# STM32-E407_Rev_B1.net
KiCad netlist of a schematic drawn in EAGLE
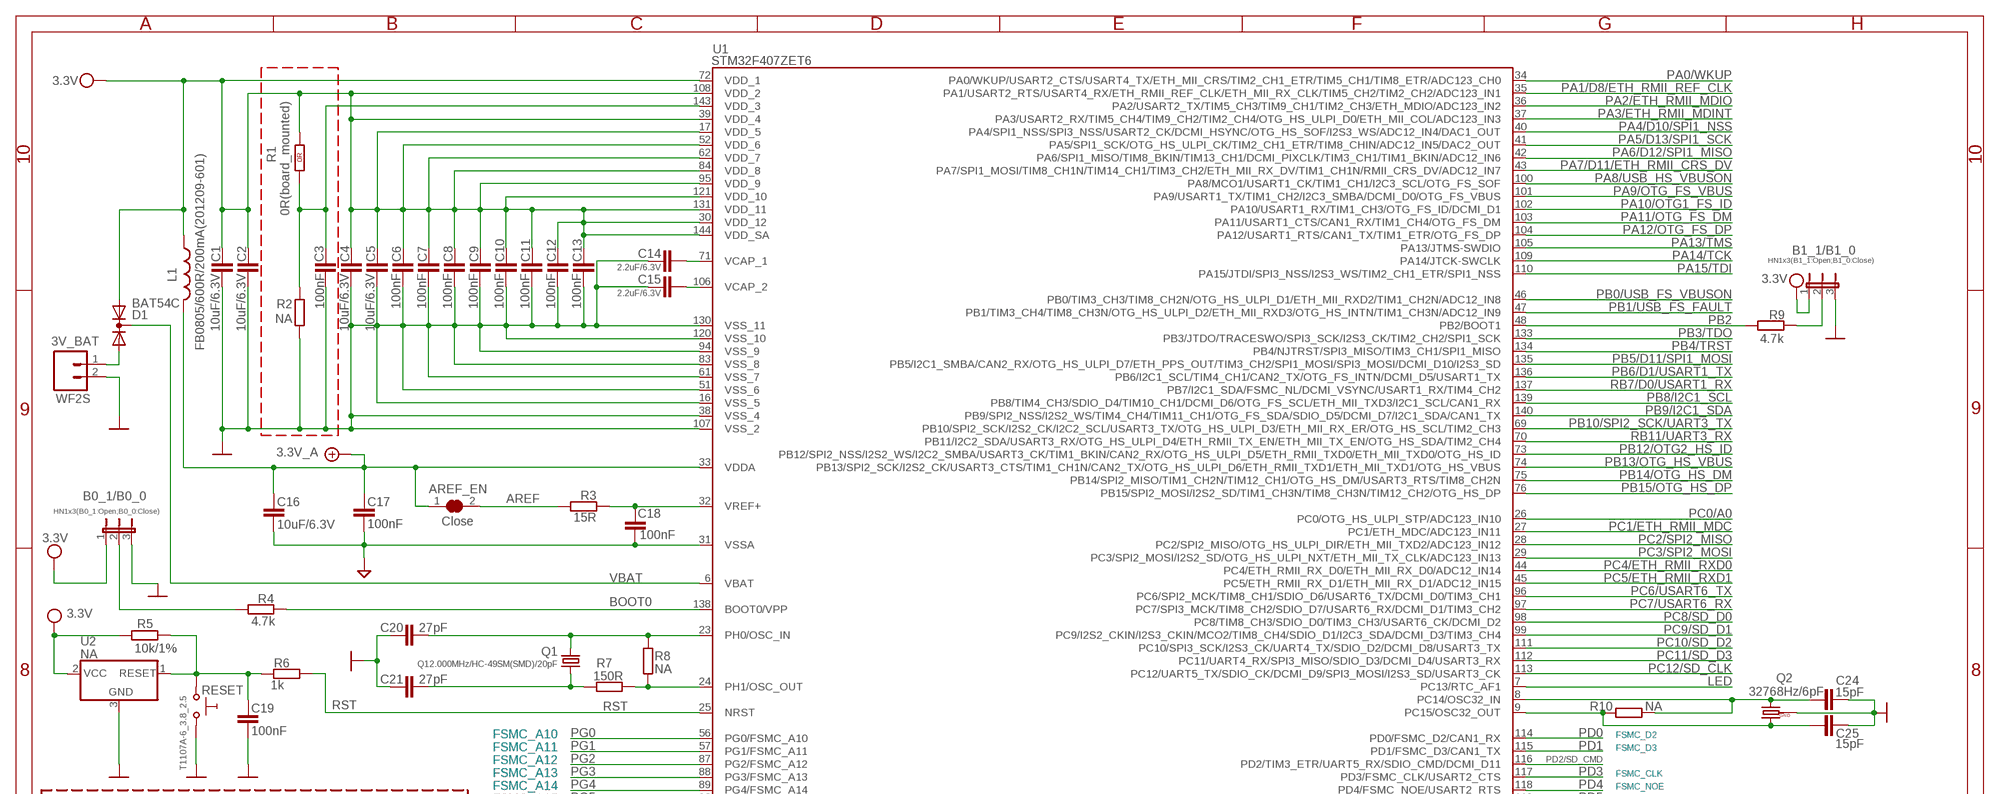
[diagram p0: schematic, sheet 1, part 1 of 2]
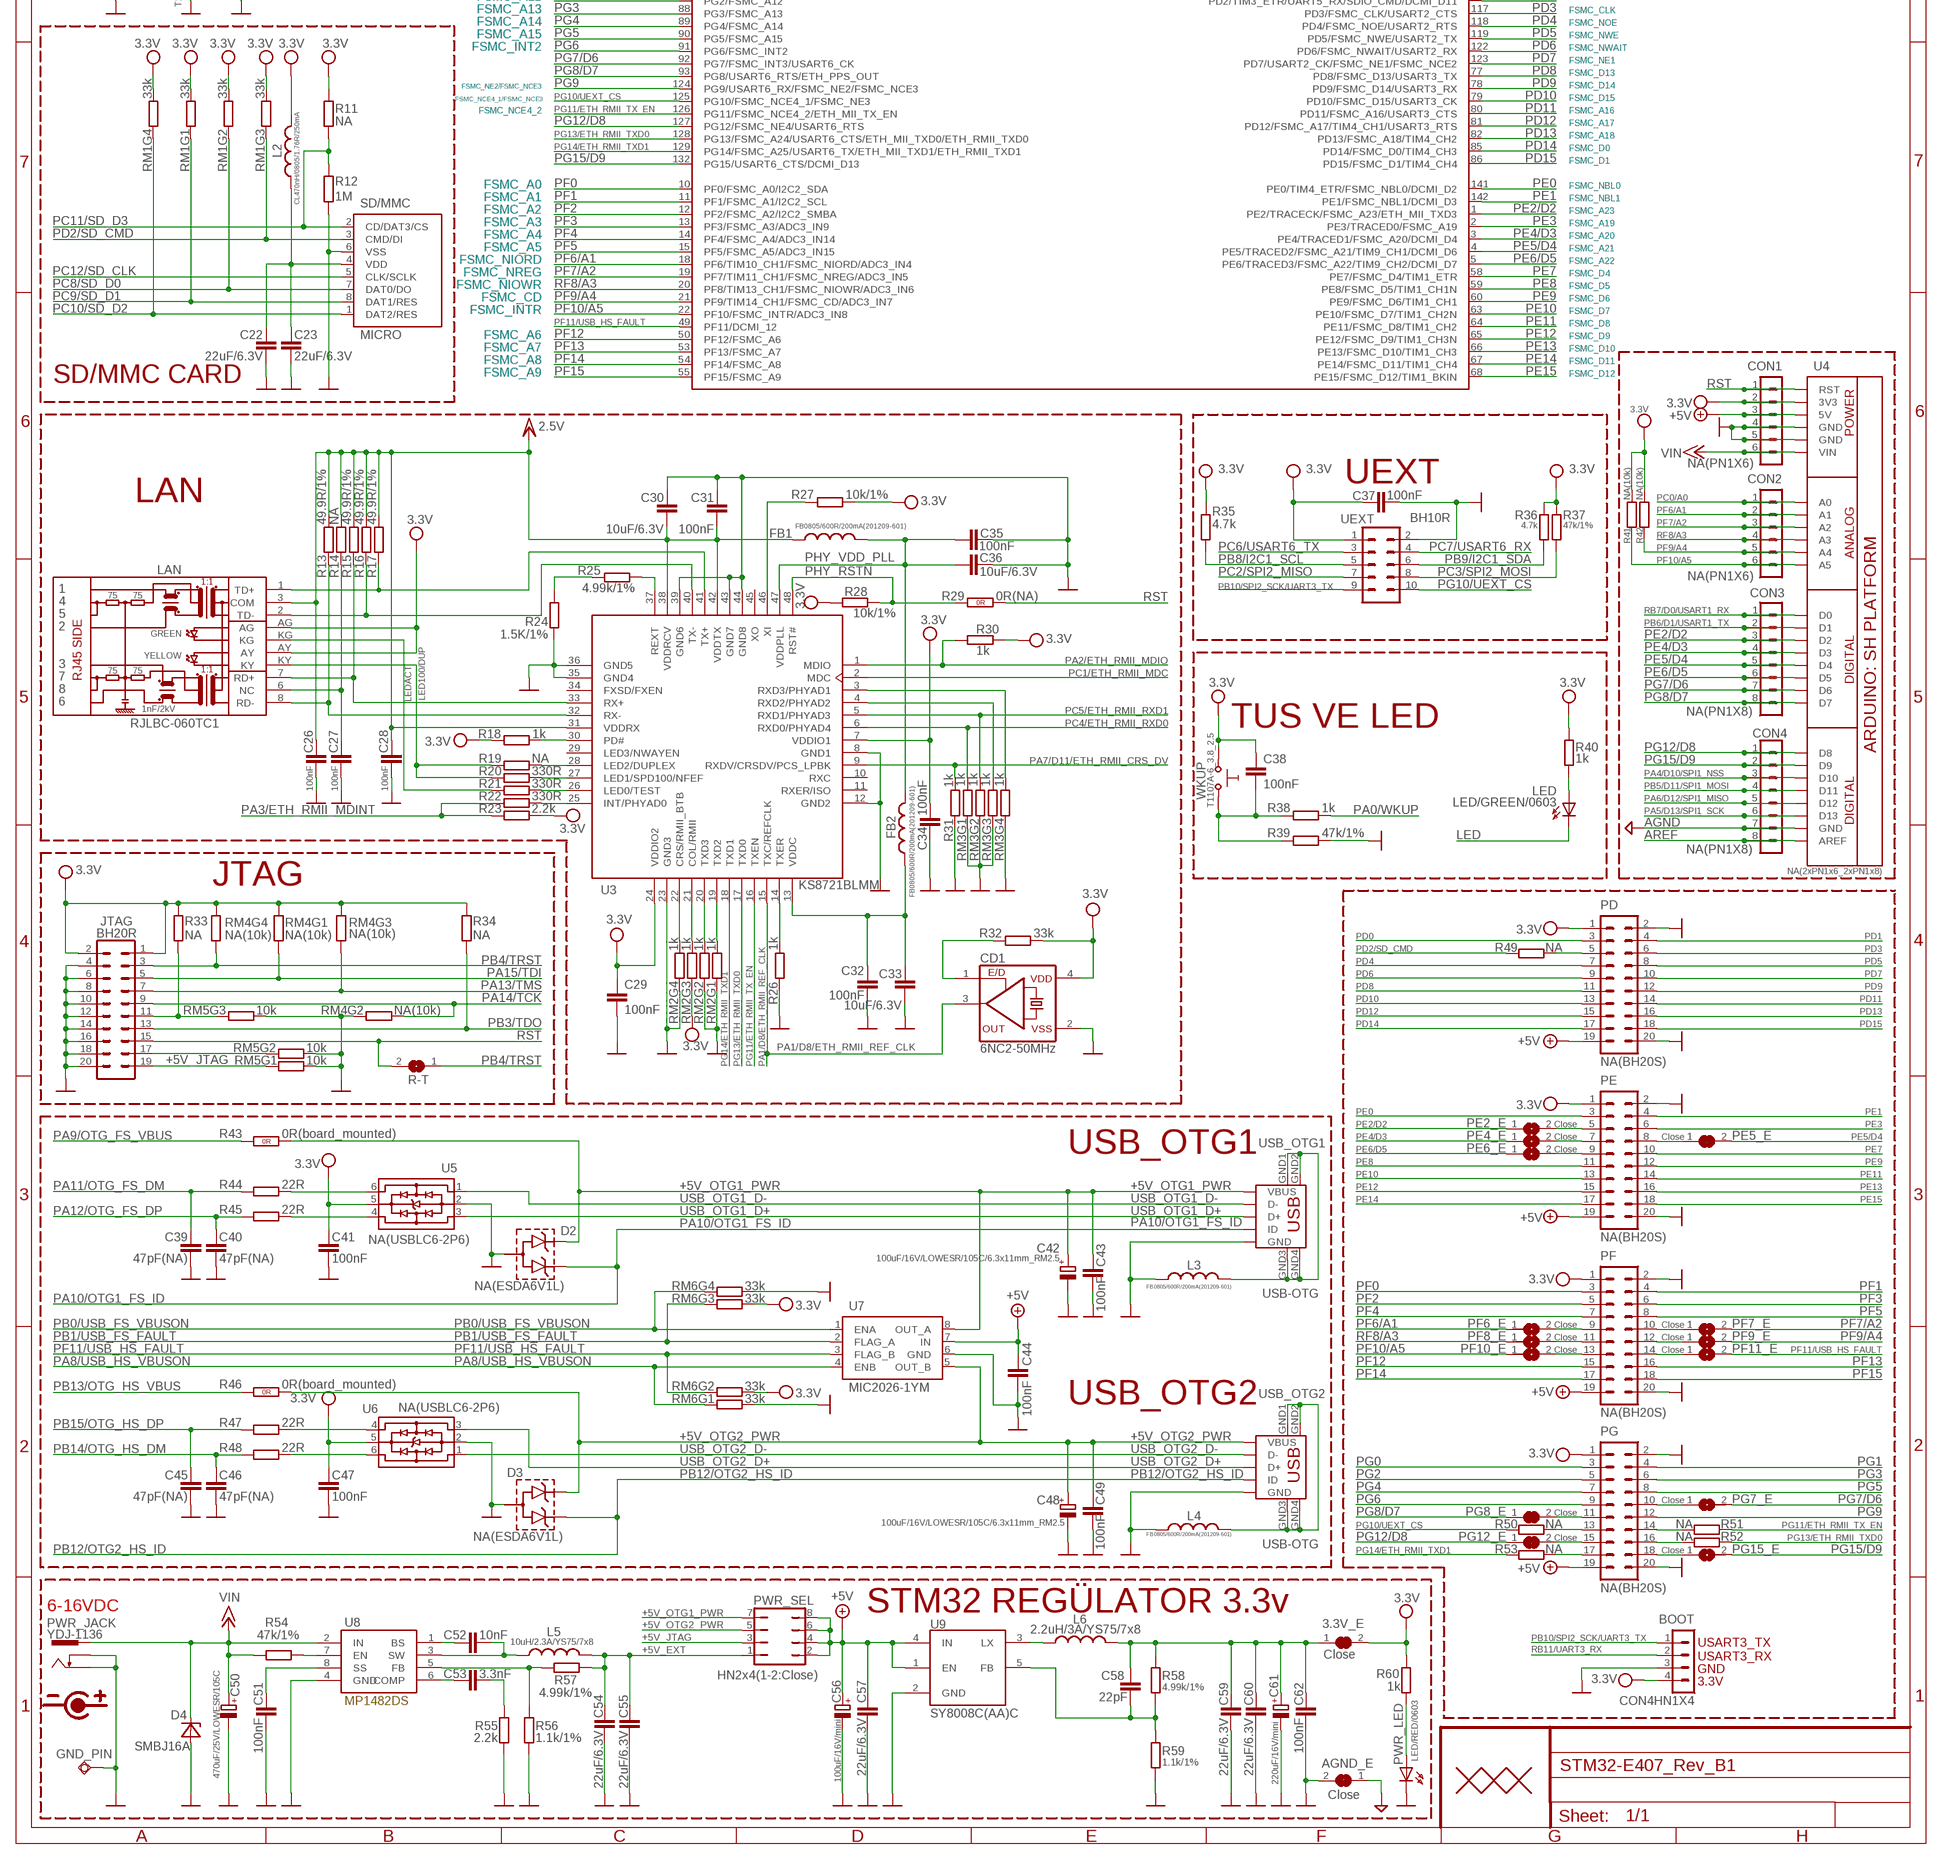
[diagram p1: schematic, sheet 1, part 2 of 2]

(export (version "E")
  (design (tool "Eeschema 10.0.6"))
  (components
    (comp (ref "3.3V_E")
      (value "Close")
      (footprint "eagle-import:SJ_1_SMALLER_CLOSE")
      (libsource (lib "eagle-import") (part "SJSJ_1_SMALLER_CLOSE"))
    )
    (comp (ref "3V_BAT")
      (value "WF2S")
      (footprint "eagle-import:CON2.54MM-2-0")
      (libsource (lib "eagle-import") (part "CON2PV2-2.54MM"))
    )
    (comp (ref "AGND_E")
      (value "Close")
      (footprint "eagle-import:SJ_1_SMALLER_CLOSE")
      (libsource (lib "eagle-import") (part "SJSJ_1_SMALLER_CLOSE"))
    )
    (comp (ref "AREF_EN")
      (value "Close")
      (footprint "eagle-import:SJ_1_SMALLER_CLOSE")
      (libsource (lib "eagle-import") (part "SJSJ_1_SMALLER_CLOSE"))
    )
    (comp (ref "B0_1/B0_0")
      (value "HN1x3(B0_1:Open;B0_0:Close)")
      (footprint "eagle-import:JP2")
      (libsource (lib "eagle-import") (part "JP2E"))
    )
    (comp (ref "B1_1/B1_0")
      (value "HN1x3(B1_1:Open;B1_0:Close)")
      (footprint "eagle-import:JP2")
      (libsource (lib "eagle-import") (part "JP2E"))
    )
    (comp (ref "BOOT")
      (value "CON4HN1X4")
      (footprint "eagle-import:HN1X4")
      (libsource (lib "eagle-import") (part "CON4HN1X4"))
    )
    (comp (ref "C1")
      (value "10uF/6.3V")
      (footprint "eagle-import:C0603_DWS")
      (libsource (lib "eagle-import") (part "C-EUC0603_DWS"))
    )
    (comp (ref "C2")
      (value "10uF/6.3V")
      (footprint "eagle-import:C0603_DWS")
      (libsource (lib "eagle-import") (part "C-EUC0603_DWS"))
    )
    (comp (ref "C3")
      (value "100nF")
      (footprint "eagle-import:C0603_DWS")
      (libsource (lib "eagle-import") (part "C-EUC0603_DWS"))
    )
    (comp (ref "C4")
      (value "10uF/6.3V")
      (footprint "eagle-import:C0603_DWS")
      (libsource (lib "eagle-import") (part "C-EUC0603_DWS"))
    )
    (comp (ref "C5")
      (value "10uF/6.3V")
      (footprint "eagle-import:C0603_DWS")
      (libsource (lib "eagle-import") (part "C-EUC0603_DWS"))
    )
    (comp (ref "C6")
      (value "100nF")
      (footprint "eagle-import:C0603_DWS")
      (libsource (lib "eagle-import") (part "C-EUC0603_DWS"))
    )
    (comp (ref "C7")
      (value "100nF")
      (footprint "eagle-import:C0603_DWS")
      (libsource (lib "eagle-import") (part "C-EUC0603_DWS"))
    )
    (comp (ref "C8")
      (value "100nF")
      (footprint "eagle-import:C0603_DWS")
      (libsource (lib "eagle-import") (part "C-EUC0603_DWS"))
    )
    (comp (ref "C9")
      (value "100nF")
      (footprint "eagle-import:C0603_DWS")
      (libsource (lib "eagle-import") (part "C-EUC0603_DWS"))
    )
    (comp (ref "C10")
      (value "100nF")
      (footprint "eagle-import:C0603_DWS")
      (libsource (lib "eagle-import") (part "C-EUC0603_DWS"))
    )
    (comp (ref "C11")
      (value "100nF")
      (footprint "eagle-import:C0603_DWS")
      (libsource (lib "eagle-import") (part "C-EUC0603_DWS"))
    )
    (comp (ref "C12")
      (value "100nF")
      (footprint "eagle-import:C0603_DWS")
      (libsource (lib "eagle-import") (part "C-EUC0603_DWS"))
    )
    (comp (ref "C13")
      (value "100nF")
      (footprint "eagle-import:C0603_DWS")
      (libsource (lib "eagle-import") (part "C-EUC0603_DWS"))
    )
    (comp (ref "C14")
      (value "2.2uF/6.3V")
      (footprint "eagle-import:C0603_DWS")
      (libsource (lib "eagle-import") (part "C-EUC0603_DWS"))
    )
    (comp (ref "C15")
      (value "2.2uF/6.3V")
      (footprint "eagle-import:C0603_DWS")
      (libsource (lib "eagle-import") (part "C-EUC0603_DWS"))
    )
    (comp (ref "C16")
      (value "10uF/6.3V")
      (footprint "eagle-import:C0603_DWS")
      (libsource (lib "eagle-import") (part "C-EUC0603_DWS"))
    )
    (comp (ref "C17")
      (value "100nF")
      (footprint "eagle-import:C0603_DWS")
      (libsource (lib "eagle-import") (part "C-EUC0603_DWS"))
    )
    (comp (ref "C18")
      (value "100nF")
      (footprint "eagle-import:C0603_DWS")
      (libsource (lib "eagle-import") (part "C-EUC0603_DWS"))
    )
    (comp (ref "C19")
      (value "100nF")
      (footprint "eagle-import:C0603_DWS")
      (libsource (lib "eagle-import") (part "C-EUC0603_DWS"))
    )
    (comp (ref "C20")
      (value "27pF")
      (footprint "eagle-import:C0603_DWS")
      (libsource (lib "eagle-import") (part "C-EUC0603_DWS"))
    )
    (comp (ref "C21")
      (value "27pF")
      (footprint "eagle-import:C0603_DWS")
      (libsource (lib "eagle-import") (part "C-EUC0603_DWS"))
    )
    (comp (ref "C22")
      (value "22uF/6.3V")
      (footprint "eagle-import:C0603_DWS")
      (libsource (lib "eagle-import") (part "C-EUC0603_DWS"))
    )
    (comp (ref "C23")
      (value "22uF/6.3V")
      (footprint "eagle-import:C0603_DWS")
      (libsource (lib "eagle-import") (part "C-EUC0603_DWS"))
    )
    (comp (ref "C24")
      (value "15pF")
      (footprint "eagle-import:C0603_DWS")
      (libsource (lib "eagle-import") (part "C-EUC0603_DWS"))
    )
    (comp (ref "C25")
      (value "15pF")
      (footprint "eagle-import:C0603_DWS")
      (libsource (lib "eagle-import") (part "C-EUC0603_DWS"))
    )
    (comp (ref "C26")
      (value "100nF")
      (footprint "eagle-import:C0603_DWS")
      (libsource (lib "eagle-import") (part "C-EUC0603_DWS"))
    )
    (comp (ref "C27")
      (value "100nF")
      (footprint "eagle-import:C0603_DWS")
      (libsource (lib "eagle-import") (part "C-EUC0603_DWS"))
    )
    (comp (ref "C28")
      (value "100nF")
      (footprint "eagle-import:C0603_DWS")
      (libsource (lib "eagle-import") (part "C-EUC0603_DWS"))
    )
    (comp (ref "C29")
      (value "100nF")
      (footprint "eagle-import:C0603_DWS")
      (libsource (lib "eagle-import") (part "C-EUC0603_DWS"))
    )
    (comp (ref "C30")
      (value "10uF/6.3V")
      (footprint "eagle-import:C0603_DWS")
      (libsource (lib "eagle-import") (part "C-EUC0603_DWS"))
    )
    (comp (ref "C31")
      (value "100nF")
      (footprint "eagle-import:C0603_DWS")
      (libsource (lib "eagle-import") (part "C-EUC0603_DWS"))
    )
    (comp (ref "C32")
      (value "100nF")
      (footprint "eagle-import:C0603_DWS")
      (libsource (lib "eagle-import") (part "C-EUC0603_DWS"))
    )
    (comp (ref "C33")
      (value "10uF/6.3V")
      (footprint "eagle-import:C0603_DWS")
      (libsource (lib "eagle-import") (part "C-EUC0603_DWS"))
    )
    (comp (ref "C34")
      (value "100nF")
      (footprint "eagle-import:C0603_DWS")
      (libsource (lib "eagle-import") (part "C-EUC0603_DWS"))
    )
    (comp (ref "C35")
      (value "100nF")
      (footprint "eagle-import:C0603_DWS")
      (libsource (lib "eagle-import") (part "C-EUC0603_DWS"))
    )
    (comp (ref "C36")
      (value "10uF/6.3V")
      (footprint "eagle-import:C0603_DWS")
      (libsource (lib "eagle-import") (part "C-EUC0603_DWS"))
    )
    (comp (ref "C37")
      (value "100nF")
      (footprint "eagle-import:C0603_DWS")
      (libsource (lib "eagle-import") (part "C-EUC0603_DWS"))
    )
    (comp (ref "C38")
      (value "100nF")
      (footprint "eagle-import:C0603_DWS")
      (libsource (lib "eagle-import") (part "C-EUC0603_DWS"))
    )
    (comp (ref "C39")
      (value "47pF(NA)")
      (footprint "eagle-import:C0603_DWS")
      (libsource (lib "eagle-import") (part "C-EUC0603_DWS"))
    )
    (comp (ref "C40")
      (value "47pF(NA)")
      (footprint "eagle-import:C0603_DWS")
      (libsource (lib "eagle-import") (part "C-EUC0603_DWS"))
    )
    (comp (ref "C41")
      (value "100nF")
      (footprint "eagle-import:C0603_DWS")
      (libsource (lib "eagle-import") (part "C-EUC0603_DWS"))
    )
    (comp (ref "C42")
      (value "100uF/16V/LOWESR/105C/6.3x11mm_RM2.5")
      (footprint "eagle-import:E2,5-6,3")
      (libsource (lib "eagle-import") (part "CPOL-EUE2.5-6.3"))
    )
    (comp (ref "C43")
      (value "100nF")
      (footprint "eagle-import:C0603_DWS")
      (libsource (lib "eagle-import") (part "C-EUC0603_DWS"))
    )
    (comp (ref "C44")
      (value "100nF")
      (footprint "eagle-import:C0603_DWS")
      (libsource (lib "eagle-import") (part "C-EUC0603_DWS"))
    )
    (comp (ref "C45")
      (value "47pF(NA)")
      (footprint "eagle-import:C0603_DWS")
      (libsource (lib "eagle-import") (part "C-EUC0603_DWS"))
    )
    (comp (ref "C46")
      (value "47pF(NA)")
      (footprint "eagle-import:C0603_DWS")
      (libsource (lib "eagle-import") (part "C-EUC0603_DWS"))
    )
    (comp (ref "C47")
      (value "100nF")
      (footprint "eagle-import:C0603_DWS")
      (libsource (lib "eagle-import") (part "C-EUC0603_DWS"))
    )
    (comp (ref "C48")
      (value "100uF/16V/LOWESR/105C/6.3x11mm_RM2.5")
      (footprint "eagle-import:E2,5-6,3")
      (libsource (lib "eagle-import") (part "CPOL-EUE2.5-6.3"))
    )
    (comp (ref "C49")
      (value "100nF")
      (footprint "eagle-import:C0603_DWS")
      (libsource (lib "eagle-import") (part "C-EUC0603_DWS"))
    )
    (comp (ref "C50")
      (value "470uF/25V/LOWESR/105C")
      (footprint "eagle-import:E5-10,5")
      (libsource (lib "eagle-import") (part "CPOL-EUE5-10.5"))
    )
    (comp (ref "C51")
      (value "100nF")
      (footprint "eagle-import:C0603_DWS")
      (libsource (lib "eagle-import") (part "C-EUC0603_DWS"))
    )
    (comp (ref "C52")
      (value "10nF")
      (footprint "eagle-import:C0603_DWS")
      (libsource (lib "eagle-import") (part "C-EUC0603_DWS"))
    )
    (comp (ref "C53")
      (value "3.3nF")
      (footprint "eagle-import:C0603_DWS")
      (libsource (lib "eagle-import") (part "C-EUC0603_DWS"))
    )
    (comp (ref "C54")
      (value "22uF/6.3V")
      (footprint "eagle-import:C0603_DWS")
      (libsource (lib "eagle-import") (part "C-EUC0603_DWS"))
    )
    (comp (ref "C55")
      (value "22uF/6.3V")
      (footprint "eagle-import:C0603_DWS")
      (libsource (lib "eagle-import") (part "C-EUC0603_DWS"))
    )
    (comp (ref "C56")
      (value "100uF/16V/mini")
      (footprint "eagle-import:E2,5-6")
      (libsource (lib "eagle-import") (part "CPOL-EUE2.5-6"))
    )
    (comp (ref "C57")
      (value "22uF/6.3V")
      (footprint "eagle-import:C0603_DWS")
      (libsource (lib "eagle-import") (part "C-EUC0603_DWS"))
    )
    (comp (ref "C58")
      (value "22pF")
      (footprint "eagle-import:C0603_DWS")
      (libsource (lib "eagle-import") (part "C-EUC0603_DWS"))
    )
    (comp (ref "C59")
      (value "22uF/6.3V")
      (footprint "eagle-import:C0603_DWS")
      (libsource (lib "eagle-import") (part "C-EUC0603_DWS"))
    )
    (comp (ref "C60")
      (value "22uF/6.3V")
      (footprint "eagle-import:C0603_DWS")
      (libsource (lib "eagle-import") (part "C-EUC0603_DWS"))
    )
    (comp (ref "C61")
      (value "220uF/16V/mini")
      (footprint "eagle-import:E3,5-8")
      (libsource (lib "eagle-import") (part "CPOL-EUE3.5-8"))
    )
    (comp (ref "C62")
      (value "100nF")
      (footprint "eagle-import:C0603_DWS")
      (libsource (lib "eagle-import") (part "C-EUC0603_DWS"))
    )
    (comp (ref "CD1")
      (value "6NC2-50MHz")
      (footprint "eagle-import:7X5MM_CLOCK_DRIVER")
      (libsource (lib "eagle-import") (part "6NC2_CLOCK_DRIVER"))
    )
    (comp (ref "CON1")
      (value "NA(PN1X6)")
      (footprint "eagle-import:PN1X6")
      (libsource (lib "eagle-import") (part "CON6PN1X6"))
    )
    (comp (ref "CON2")
      (value "NA(PN1X6)")
      (footprint "eagle-import:PN1X6")
      (libsource (lib "eagle-import") (part "CON6PN1X6"))
    )
    (comp (ref "CON3")
      (value "NA(PN1X8)")
      (footprint "eagle-import:PN1X8")
      (libsource (lib "eagle-import") (part "CON8PN1X8"))
    )
    (comp (ref "CON4")
      (value "NA(PN1X8)")
      (footprint "eagle-import:PN1X8")
      (libsource (lib "eagle-import") (part "CON8PN1X8"))
    )
    (comp (ref "D1")
      (value "BAT54C")
      (footprint "eagle-import:SOT23C")
      (libsource (lib "eagle-import") (part "DIODE_AC-CA_"))
    )
    (comp (ref "D2")
      (value "NA(ESDA6V1L)")
      (footprint "eagle-import:SOT-23")
      (libsource (lib "eagle-import") (part "MMBZ5V6ALT1"))
    )
    (comp (ref "D3")
      (value "NA(ESDA6V1L)")
      (footprint "eagle-import:SOT-23")
      (libsource (lib "eagle-import") (part "MMBZ5V6ALT1"))
    )
    (comp (ref "D4")
      (value "SMBJ16A")
      (footprint "eagle-import:DO214AA")
      (libsource (lib "eagle-import") (part "SMBJ16A"))
    )
    (comp (ref "FB1")
      (value "FB0805/600R/200mA(201209-601)")
      (footprint "eagle-import:L0805_5MIL_DWS")
      (libsource (lib "eagle-import") (part "L-USL0805_5MIL_DWS"))
    )
    (comp (ref "FB2")
      (value "FB0805/600R/200mA(201209-601)")
      (footprint "eagle-import:L0805_5MIL_DWS")
      (libsource (lib "eagle-import") (part "L-USL0805_5MIL_DWS"))
    )
    (comp (ref "GND_PIN")
      (value "TESTPAD3")
      (footprint "eagle-import:TEST_PAD40_70_SQUARE")
      (libsource (lib "eagle-import") (part "TESTPAD3"))
    )
    (comp (ref "JTAG")
      (value "BH20R")
      (footprint "eagle-import:BH20R")
      (libsource (lib "eagle-import") (part "ML20R"))
    )
    (comp (ref "L1")
      (value "FB0805/600R/200mA(201209-601)")
      (footprint "eagle-import:L0805_5MIL_DWS")
      (libsource (lib "eagle-import") (part "L-USL0805_5MIL_DWS"))
    )
    (comp (ref "L2")
      (value "CL470nH/0805/1.76R/250mA")
      (footprint "eagle-import:L0805_5MIL_DWS")
      (libsource (lib "eagle-import") (part "L-USL0805_5MIL_DWS"))
    )
    (comp (ref "L3")
      (value "FB0805/600R/200mA(201209-601)")
      (footprint "eagle-import:L0805_5MIL_DWS")
      (libsource (lib "eagle-import") (part "L-USL0805_5MIL_DWS"))
    )
    (comp (ref "L4")
      (value "FB0805/600R/200mA(201209-601)")
      (footprint "eagle-import:L0805_5MIL_DWS")
      (libsource (lib "eagle-import") (part "L-USL0805_5MIL_DWS"))
    )
    (comp (ref "L5")
      (value "10uH/2.3A/YS75/7x8")
      (footprint "eagle-import:L7078")
      (libsource (lib "eagle-import") (part "L-USL7078"))
    )
    (comp (ref "L6")
      (value "2.2uH/3A/YS75/7x8")
      (footprint "eagle-import:L7078")
      (libsource (lib "eagle-import") (part "L-USL7078"))
    )
    (comp (ref "LAN")
      (value "RJLBC-060TC1")
      (footprint "eagle-import:RJLBC-060TC1")
      (libsource (lib "eagle-import") (part "RJLBC-060TC1"))
    )
    (comp (ref "LED")
      (value "LED/GREEN/0603")
      (footprint "eagle-import:LED-0603")
      (libsource (lib "eagle-import") (part "LED0603DWS"))
    )
    (comp (ref "PD")
      (value "NA(BH20S)")
      (footprint "eagle-import:ML20-MALE")
      (libsource (lib "eagle-import") (part "ML20"))
    )
    (comp (ref "PE")
      (value "NA(BH20S)")
      (footprint "eagle-import:ML20-MALE")
      (libsource (lib "eagle-import") (part "ML20"))
    )
    (comp (ref "PE2_E")
      (value "Close")
      (footprint "eagle-import:SJ_1_SMALLER_CLOSE")
      (libsource (lib "eagle-import") (part "SJSJ_1_SMALLER_CLOSE"))
    )
    (comp (ref "PE4_E")
      (value "Close")
      (footprint "eagle-import:SJ_1_SMALLER_CLOSE")
      (libsource (lib "eagle-import") (part "SJSJ_1_SMALLER_CLOSE"))
    )
    (comp (ref "PE5_E")
      (value "Close")
      (footprint "eagle-import:SJ_1_SMALLER_CLOSE")
      (libsource (lib "eagle-import") (part "SJSJ_1_SMALLER_CLOSE"))
    )
    (comp (ref "PE6_E")
      (value "Close")
      (footprint "eagle-import:SJ_1_SMALLER_CLOSE")
      (libsource (lib "eagle-import") (part "SJSJ_1_SMALLER_CLOSE"))
    )
    (comp (ref "PF")
      (value "NA(BH20S)")
      (footprint "eagle-import:ML20-MALE")
      (libsource (lib "eagle-import") (part "ML20"))
    )
    (comp (ref "PF6_E")
      (value "Close")
      (footprint "eagle-import:SJ_1_SMALLER_CLOSE")
      (libsource (lib "eagle-import") (part "SJSJ_1_SMALLER_CLOSE"))
    )
    (comp (ref "PF7_E")
      (value "Close")
      (footprint "eagle-import:SJ_1_SMALLER_CLOSE")
      (libsource (lib "eagle-import") (part "SJSJ_1_SMALLER_CLOSE"))
    )
    (comp (ref "PF8_E")
      (value "Close")
      (footprint "eagle-import:SJ_1_SMALLER_CLOSE")
      (libsource (lib "eagle-import") (part "SJSJ_1_SMALLER_CLOSE"))
    )
    (comp (ref "PF9_E")
      (value "Close")
      (footprint "eagle-import:SJ_1_SMALLER_CLOSE")
      (libsource (lib "eagle-import") (part "SJSJ_1_SMALLER_CLOSE"))
    )
    (comp (ref "PF10_E")
      (value "Close")
      (footprint "eagle-import:SJ_1_SMALLER_CLOSE")
      (libsource (lib "eagle-import") (part "SJSJ_1_SMALLER_CLOSE"))
    )
    (comp (ref "PF11_E")
      (value "Close")
      (footprint "eagle-import:SJ_1_SMALLER_CLOSE")
      (libsource (lib "eagle-import") (part "SJSJ_1_SMALLER_CLOSE"))
    )
    (comp (ref "PG")
      (value "NA(BH20S)")
      (footprint "eagle-import:ML20-MALE")
      (libsource (lib "eagle-import") (part "ML20"))
    )
    (comp (ref "PG7_E")
      (value "Close")
      (footprint "eagle-import:SJ_1_SMALLER_CLOSE")
      (libsource (lib "eagle-import") (part "SJSJ_1_SMALLER_CLOSE"))
    )
    (comp (ref "PG8_E")
      (value "Close")
      (footprint "eagle-import:SJ_1_SMALLER_CLOSE")
      (libsource (lib "eagle-import") (part "SJSJ_1_SMALLER_CLOSE"))
    )
    (comp (ref "PG12_E")
      (value "Close")
      (footprint "eagle-import:SJ_1_SMALLER_CLOSE")
      (libsource (lib "eagle-import") (part "SJSJ_1_SMALLER_CLOSE"))
    )
    (comp (ref "PG15_E")
      (value "Close")
      (footprint "eagle-import:SJ_1_SMALLER_CLOSE")
      (libsource (lib "eagle-import") (part "SJSJ_1_SMALLER_CLOSE"))
    )
    (comp (ref "PWR_JACK")
      (value "YDJ-1136")
      (footprint "eagle-import:PWR_JACK_UNI_MILLING")
      (libsource (lib "eagle-import") (part "PWR-JAKPWR_JACK_UNI_MILLING"))
    )
    (comp (ref "PWR_LED")
      (value "LED/RED/0603")
      (footprint "eagle-import:LED-0603")
      (libsource (lib "eagle-import") (part "LED0603DWS"))
    )
    (comp (ref "PWR_SEL")
      (value "HN2x4(1-2:Close)")
      (footprint "eagle-import:JP4Q_2")
      (libsource (lib "eagle-import") (part "JP4QNEW"))
    )
    (comp (ref "Q1")
      (value "Q12.000MHz/HC-49SM(SMD)/20pF")
      (footprint "eagle-import:HC49_SMD2_THIN")
      (libsource (lib "eagle-import") (part "HC49/S1"))
    )
    (comp (ref "Q2")
      (value "32768Hz/6pF")
      (footprint "eagle-import:TC26H_3_REPAIR_SMD")
      (libsource (lib "eagle-import") (part "Q_GND1"))
    )
    (comp (ref "R-T")
      (value "Open")
      (footprint "eagle-import:SJ_1_SMALLER")
      (libsource (lib "eagle-import") (part "SJSJ_SMALLER"))
    )
    (comp (ref "R1")
      (value "0R(board_mounted)")
      (footprint "eagle-import:0603_0R")
      (libsource (lib "eagle-import") (part "R_0R0R(NA)"))
    )
    (comp (ref "R2")
      (value "NA")
      (footprint "eagle-import:R0603_5MIL_DWS_NA")
      (libsource (lib "eagle-import") (part "R-EU_R0603_5MIL_DWS_NA"))
    )
    (comp (ref "R3")
      (value "15R")
      (footprint "eagle-import:R0603_5MIL_DWS")
      (libsource (lib "eagle-import") (part "R-EU_R0603_5MIL_DWS"))
    )
    (comp (ref "R4")
      (value "4.7k")
      (footprint "eagle-import:R0603_5MIL_DWS")
      (libsource (lib "eagle-import") (part "R-EU_R0603_5MIL_DWS"))
    )
    (comp (ref "R5")
      (value "10k/1%")
      (footprint "eagle-import:R0603_5MIL_DWS")
      (libsource (lib "eagle-import") (part "R-EU_R0603_5MIL_DWS"))
    )
    (comp (ref "R6")
      (value "1k")
      (footprint "eagle-import:R0603_5MIL_DWS")
      (libsource (lib "eagle-import") (part "R-EU_R0603_5MIL_DWS"))
    )
    (comp (ref "R7")
      (value "150R")
      (footprint "eagle-import:R0603_5MIL_DWS")
      (libsource (lib "eagle-import") (part "R-EU_R0603_5MIL_DWS"))
    )
    (comp (ref "R8")
      (value "NA")
      (footprint "eagle-import:R0603_5MIL_DWS_NA")
      (libsource (lib "eagle-import") (part "R-EU_R0603_5MIL_DWS_NA"))
    )
    (comp (ref "R9")
      (value "4.7k")
      (footprint "eagle-import:R0603_5MIL_DWS")
      (libsource (lib "eagle-import") (part "R-EU_R0603_5MIL_DWS"))
    )
    (comp (ref "R10")
      (value "NA")
      (footprint "eagle-import:R0603_5MIL_DWS_NA")
      (libsource (lib "eagle-import") (part "R-EU_R0603_5MIL_DWS_NA"))
    )
    (comp (ref "R11")
      (value "NA")
      (footprint "eagle-import:R0603_5MIL_DWS_NA")
      (libsource (lib "eagle-import") (part "R-EU_R0603_5MIL_DWS_NA"))
    )
    (comp (ref "R12")
      (value "1M")
      (footprint "eagle-import:R0603_5MIL_DWS")
      (libsource (lib "eagle-import") (part "R-EU_R0603_5MIL_DWS"))
    )
    (comp (ref "R13")
      (value "49.9R/1%")
      (footprint "eagle-import:R0603_5MIL_DWS")
      (libsource (lib "eagle-import") (part "R-EU_R0603_5MIL_DWS"))
    )
    (comp (ref "R14")
      (value "NA")
      (footprint "eagle-import:R0603_5MIL_DWS_NA")
      (libsource (lib "eagle-import") (part "R-EU_R0603_5MIL_DWS_NA"))
    )
    (comp (ref "R15")
      (value "49.9R/1%")
      (footprint "eagle-import:R0603_5MIL_DWS")
      (libsource (lib "eagle-import") (part "R-EU_R0603_5MIL_DWS"))
    )
    (comp (ref "R16")
      (value "49.9R/1%")
      (footprint "eagle-import:R0603_5MIL_DWS")
      (libsource (lib "eagle-import") (part "R-EU_R0603_5MIL_DWS"))
    )
    (comp (ref "R17")
      (value "49.9R/1%")
      (footprint "eagle-import:R0603_5MIL_DWS")
      (libsource (lib "eagle-import") (part "R-EU_R0603_5MIL_DWS"))
    )
    (comp (ref "R18")
      (value "1k")
      (footprint "eagle-import:R0603_5MIL_DWS")
      (libsource (lib "eagle-import") (part "R-EU_R0603_5MIL_DWS"))
    )
    (comp (ref "R19")
      (value "NA")
      (footprint "eagle-import:R0603_5MIL_DWS_NA")
      (libsource (lib "eagle-import") (part "R-EU_R0603_5MIL_DWS_NA"))
    )
    (comp (ref "R20")
      (value "330R")
      (footprint "eagle-import:R0603_5MIL_DWS")
      (libsource (lib "eagle-import") (part "R-EU_R0603_5MIL_DWS"))
    )
    (comp (ref "R21")
      (value "330R")
      (footprint "eagle-import:R0603_5MIL_DWS")
      (libsource (lib "eagle-import") (part "R-EU_R0603_5MIL_DWS"))
    )
    (comp (ref "R22")
      (value "330R")
      (footprint "eagle-import:R0603_5MIL_DWS")
      (libsource (lib "eagle-import") (part "R-EU_R0603_5MIL_DWS"))
    )
    (comp (ref "R23")
      (value "2.2k")
      (footprint "eagle-import:R0603_5MIL_DWS")
      (libsource (lib "eagle-import") (part "R-EU_R0603_5MIL_DWS"))
    )
    (comp (ref "R24")
      (value "1.5K/1%")
      (footprint "eagle-import:R0603_5MIL_DWS")
      (libsource (lib "eagle-import") (part "R-EU_R0603_5MIL_DWS"))
    )
    (comp (ref "R25")
      (value "4.99k/1%")
      (footprint "eagle-import:R0603_5MIL_DWS")
      (libsource (lib "eagle-import") (part "R-EU_R0603_5MIL_DWS"))
    )
    (comp (ref "R26")
      (value "1k")
      (footprint "eagle-import:R0603_5MIL_DWS")
      (libsource (lib "eagle-import") (part "R-EU_R0603_5MIL_DWS"))
    )
    (comp (ref "R27")
      (value "10k/1%")
      (footprint "eagle-import:R0603_5MIL_DWS")
      (libsource (lib "eagle-import") (part "R-EU_R0603_5MIL_DWS"))
    )
    (comp (ref "R28")
      (value "10k/1%")
      (footprint "eagle-import:R0603_5MIL_DWS")
      (libsource (lib "eagle-import") (part "R-EU_R0603_5MIL_DWS"))
    )
    (comp (ref "R29")
      (value "0R(NA)")
      (footprint "eagle-import:0603_0R")
      (libsource (lib "eagle-import") (part "R_0R0R(NA)"))
    )
    (comp (ref "R30")
      (value "1k")
      (footprint "eagle-import:R0603_5MIL_DWS")
      (libsource (lib "eagle-import") (part "R-EU_R0603_5MIL_DWS"))
    )
    (comp (ref "R31")
      (value "1k")
      (footprint "eagle-import:R0603_5MIL_DWS")
      (libsource (lib "eagle-import") (part "R-EU_R0603_5MIL_DWS"))
    )
    (comp (ref "R32")
      (value "33k")
      (footprint "eagle-import:R0603_5MIL_DWS")
      (libsource (lib "eagle-import") (part "R-EU_R0603_5MIL_DWS"))
    )
    (comp (ref "R33")
      (value "NA")
      (footprint "eagle-import:R0603_5MIL_DWS_NA")
      (libsource (lib "eagle-import") (part "R-EU_R0603_5MIL_DWS_NA"))
    )
    (comp (ref "R34")
      (value "NA")
      (footprint "eagle-import:R0603_5MIL_DWS_NA")
      (libsource (lib "eagle-import") (part "R-EU_R0603_5MIL_DWS_NA"))
    )
    (comp (ref "R35")
      (value "4.7k")
      (footprint "eagle-import:R0603_5MIL_DWS")
      (libsource (lib "eagle-import") (part "R-EU_R0603_5MIL_DWS"))
    )
    (comp (ref "R36")
      (value "4.7k")
      (footprint "eagle-import:R0603_5MIL_DWS")
      (libsource (lib "eagle-import") (part "R-EU_R0603_5MIL_DWS"))
    )
    (comp (ref "R37")
      (value "47k/1%")
      (footprint "eagle-import:R0603_5MIL_DWS")
      (libsource (lib "eagle-import") (part "R-EU_R0603_5MIL_DWS"))
    )
    (comp (ref "R38")
      (value "1k")
      (footprint "eagle-import:R0603_5MIL_DWS")
      (libsource (lib "eagle-import") (part "R-EU_R0603_5MIL_DWS"))
    )
    (comp (ref "R39")
      (value "47k/1%")
      (footprint "eagle-import:R0603_5MIL_DWS")
      (libsource (lib "eagle-import") (part "R-EU_R0603_5MIL_DWS"))
    )
    (comp (ref "R40")
      (value "1k")
      (footprint "eagle-import:R0603_5MIL_DWS")
      (libsource (lib "eagle-import") (part "R-EU_R0603_5MIL_DWS"))
    )
    (comp (ref "R41")
      (value "NA(10k)")
      (footprint "eagle-import:R0603_5MIL_DWS_NA")
      (libsource (lib "eagle-import") (part "R-EU_R0603_5MIL_DWS_NA"))
    )
    (comp (ref "R42")
      (value "NA(10k)")
      (footprint "eagle-import:R0603_5MIL_DWS_NA")
      (libsource (lib "eagle-import") (part "R-EU_R0603_5MIL_DWS_NA"))
    )
    (comp (ref "R43")
      (value "0R(board_mounted)")
      (footprint "eagle-import:0603_0R")
      (libsource (lib "eagle-import") (part "R_0R0R(NA)"))
    )
    (comp (ref "R44")
      (value "22R")
      (footprint "eagle-import:R0603_5MIL_DWS")
      (libsource (lib "eagle-import") (part "R-EU_R0603_5MIL_DWS"))
    )
    (comp (ref "R45")
      (value "22R")
      (footprint "eagle-import:R0603_5MIL_DWS")
      (libsource (lib "eagle-import") (part "R-EU_R0603_5MIL_DWS"))
    )
    (comp (ref "R46")
      (value "0R(board_mounted)")
      (footprint "eagle-import:0603_0R")
      (libsource (lib "eagle-import") (part "R_0R0R(NA)"))
    )
    (comp (ref "R47")
      (value "22R")
      (footprint "eagle-import:R0603_5MIL_DWS")
      (libsource (lib "eagle-import") (part "R-EU_R0603_5MIL_DWS"))
    )
    (comp (ref "R48")
      (value "22R")
      (footprint "eagle-import:R0603_5MIL_DWS")
      (libsource (lib "eagle-import") (part "R-EU_R0603_5MIL_DWS"))
    )
    (comp (ref "R49")
      (value "NA")
      (footprint "eagle-import:R0603_5MIL_DWS")
      (libsource (lib "eagle-import") (part "R-EU_R0603_5MIL_DWS"))
    )
    (comp (ref "R50")
      (value "NA")
      (footprint "eagle-import:R0603_5MIL_DWS")
      (libsource (lib "eagle-import") (part "R-EU_R0603_5MIL_DWS"))
    )
    (comp (ref "R51")
      (value "NA")
      (footprint "eagle-import:R0603_5MIL_DWS")
      (libsource (lib "eagle-import") (part "R-EU_R0603_5MIL_DWS"))
    )
    (comp (ref "R52")
      (value "NA")
      (footprint "eagle-import:R0603_5MIL_DWS")
      (libsource (lib "eagle-import") (part "R-EU_R0603_5MIL_DWS"))
    )
    (comp (ref "R53")
      (value "NA")
      (footprint "eagle-import:R0603_5MIL_DWS")
      (libsource (lib "eagle-import") (part "R-EU_R0603_5MIL_DWS"))
    )
    (comp (ref "R54")
      (value "47k/1%")
      (footprint "eagle-import:R0603_5MIL_DWS")
      (libsource (lib "eagle-import") (part "R-EU_R0603_5MIL_DWS"))
    )
    (comp (ref "R55")
      (value "2.2k")
      (footprint "eagle-import:R0603_5MIL_DWS")
      (libsource (lib "eagle-import") (part "R-EU_R0603_5MIL_DWS"))
    )
    (comp (ref "R56")
      (value "1.1k/1%")
      (footprint "eagle-import:R0603_5MIL_DWS")
      (libsource (lib "eagle-import") (part "R-EU_R0603_5MIL_DWS"))
    )
    (comp (ref "R57")
      (value "4.99k/1%")
      (footprint "eagle-import:R0603_5MIL_DWS")
      (libsource (lib "eagle-import") (part "R-EU_R0603_5MIL_DWS"))
    )
    (comp (ref "R58")
      (value "4.99k/1%")
      (footprint "eagle-import:R0603_5MIL_DWS")
      (libsource (lib "eagle-import") (part "R-EU_R0603_5MIL_DWS"))
    )
    (comp (ref "R59")
      (value "1.1k/1%")
      (footprint "eagle-import:R0603_5MIL_DWS")
      (libsource (lib "eagle-import") (part "R-EU_R0603_5MIL_DWS"))
    )
    (comp (ref "R60")
      (value "1k")
      (footprint "eagle-import:R0603_5MIL_DWS")
      (libsource (lib "eagle-import") (part "R-EU_R0603_5MIL_DWS"))
    )
    (comp (ref "RESET")
      (value "T1107A-6_3.8_2.5")
      (footprint "eagle-import:SW-TAKT_6X3.5_SMD")
      (libsource (lib "eagle-import") (part "SW-TAKT6"))
    )
    (comp (ref "RM1")
      (value "33k")
      (footprint "eagle-import:R_MATRIX_4")
      (libsource (lib "eagle-import") (part "R_MATRIX_4E"))
    )
    (comp (ref "RM2")
      (value "1k")
      (footprint "eagle-import:R_MATRIX_4")
      (libsource (lib "eagle-import") (part "R_MATRIX_4E"))
    )
    (comp (ref "RM3")
      (value "1k")
      (footprint "eagle-import:R_MATRIX_4")
      (libsource (lib "eagle-import") (part "R_MATRIX_4E"))
    )
    (comp (ref "RM4")
      (value "NA(10k)")
      (footprint "eagle-import:R_MATRIX_4")
      (libsource (lib "eagle-import") (part "R_MATRIX_4E"))
    )
    (comp (ref "RM5")
      (value "10k")
      (footprint "eagle-import:R_MATRIX_4")
      (libsource (lib "eagle-import") (part "R_MATRIX_4E"))
    )
    (comp (ref "RM6")
      (value "33k")
      (footprint "eagle-import:R_MATRIX_4")
      (libsource (lib "eagle-import") (part "R_MATRIX_4E"))
    )
    (comp (ref "SD/MMC")
      (value "MICRO")
      (footprint "eagle-import:TFR-MEM-CON")
      (libsource (lib "eagle-import") (part "MICRO_SD/MMC"))
    )
    (comp (ref "U$1")
      (value "FIDUCIAL1X2")
      (footprint "eagle-import:FIDUCIAL-1X2")
      (libsource (lib "eagle-import") (part "FIDUCIAL1X2"))
    )
    (comp (ref "U$2")
      (value "FIDUCIAL1X2")
      (footprint "eagle-import:FIDUCIAL-1X2")
      (libsource (lib "eagle-import") (part "FIDUCIAL1X2"))
    )
    (comp (ref "U$9")
      (value "FIDUCIAL1X2")
      (footprint "eagle-import:FIDUCIAL-1X2")
      (libsource (lib "eagle-import") (part "FIDUCIAL1X2"))
    )
    (comp (ref "U1")
      (value "STM32F407ZET6")
      (footprint "eagle-import:LQFP144")
      (libsource (lib "eagle-import") (part "STM32F207ZET6"))
    )
    (comp (ref "U2")
      (value "NA")
      (footprint "eagle-import:SOT23")
      (libsource (lib "eagle-import") (part "RESETMCP130T-300-I/TT"))
    )
    (comp (ref "U3")
      (value "KS8721BLMM")
      (footprint "eagle-import:LQFP48_MM")
      (libsource (lib "eagle-import") (part "KS8721BLMM"))
    )
    (comp (ref "U4")
      (value "NA(2xPN1x6_2xPN1x8)")
      (footprint "eagle-import:ARDUINO_SHIELD_PLATFORM_WITHOUT_DIMENSION")
      (libsource (lib "eagle-import") (part "ARDUINO_SH_PLATFORM3"))
    )
    (comp (ref "U5")
      (value "NA(USBLC6-2P6)")
      (footprint "eagle-import:USBLC6-2P6")
      (libsource (lib "eagle-import") (part "USBLC6-2"))
    )
    (comp (ref "U6")
      (value "NA(USBLC6-2P6)")
      (footprint "eagle-import:USBLC6-2P6")
      (libsource (lib "eagle-import") (part "USBLC6-2"))
    )
    (comp (ref "U7")
      (value "MIC2026-1YM")
      (footprint "eagle-import:SO-8")
      (libsource (lib "eagle-import") (part "MIC2026-1YM"))
    )
    (comp (ref "U8")
      (value "MP1482DS")
      (footprint "eagle-import:SOIC8")
      (libsource (lib "eagle-import") (part "MP1482"))
    )
    (comp (ref "U9")
      (value "SY8008C(AA)C")
      (footprint "eagle-import:SOT23-5")
      (libsource (lib "eagle-import") (part "SY8008"))
    )
    (comp (ref "UEXT")
      (value "BH10R")
      (footprint "eagle-import:BH10R")
      (libsource (lib "eagle-import") (part "ML10R"))
    )
    (comp (ref "USB_OTG1")
      (value "USB-OTG")
      (footprint "eagle-import:USB_MINI_9PIN")
      (libsource (lib "eagle-import") (part "MINI_USB9"))
    )
    (comp (ref "USB_OTG2")
      (value "USB-OTG")
      (footprint "eagle-import:USB_MINI_9PIN")
      (libsource (lib "eagle-import") (part "MINI_USB9"))
    )
    (comp (ref "WKUP")
      (value "T1107A-6_3.8_2.5")
      (footprint "eagle-import:SW-TAKT_6X3.5_SMD")
      (libsource (lib "eagle-import") (part "SW-TAKT6"))
    )
  )
  (nets
    (net (code "1") (name "+5V") (class "Default")
      (node (ref "C44") (pin "1") (pinfunction "1_1") (pintype "passive"))
      (node (ref "C56") (pin "+") (pinfunction "+_+") (pintype "passive"))
      (node (ref "C57") (pin "1") (pinfunction "1_1") (pintype "passive"))
      (node (ref "CON1") (pin "3") (pinfunction "3_3") (pintype "passive"))
      (node (ref "PD") (pin "19") (pinfunction "19_19") (pintype "passive"))
      (node (ref "PE") (pin "19") (pinfunction "19_19") (pintype "passive"))
      (node (ref "PF") (pin "19") (pinfunction "19_19") (pintype "passive"))
      (node (ref "PG") (pin "19") (pinfunction "19_19") (pintype "passive"))
      (node (ref "PWR_SEL") (pin "2") (pinfunction "2_2") (pintype "passive"))
      (node (ref "PWR_SEL") (pin "4") (pinfunction "4_4") (pintype "passive"))
      (node (ref "PWR_SEL") (pin "6") (pinfunction "6_6") (pintype "passive"))
      (node (ref "PWR_SEL") (pin "8") (pinfunction "8_8") (pintype "passive"))
      (node (ref "U4") (pin "5V") (pinfunction "5V_5V") (pintype "bidirectional"))
      (node (ref "U7") (pin "7") (pinfunction "IN_7") (pintype "input"))
      (node (ref "U9") (pin "1") (pinfunction "EN_1") (pintype "bidirectional"))
      (node (ref "U9") (pin "4") (pinfunction "IN_4") (pintype "bidirectional"))
    )
    (net (code "2") (name "/+5V_EXT") (class "Default")
      (node (ref "C54") (pin "1") (pinfunction "1_1") (pintype "passive"))
      (node (ref "C55") (pin "1") (pinfunction "1_1") (pintype "passive"))
      (node (ref "L5") (pin "2") (pinfunction "2_2") (pintype "passive"))
      (node (ref "PWR_SEL") (pin "1") (pinfunction "1_1") (pintype "passive"))
      (node (ref "R57") (pin "2") (pinfunction "2_2") (pintype "passive"))
    )
    (net (code "3") (name "/+5V_JTAG") (class "Default")
      (node (ref "JTAG") (pin "19") (pinfunction "19_19") (pintype "passive"))
      (node (ref "PWR_SEL") (pin "3") (pinfunction "3_3") (pintype "passive"))
      (node (ref "RM5") (pin "1.1") (pinfunction "1_1.1") (pintype "passive"))
    )
    (net (code "4") (name "/+5V_OTG1_PWR") (class "Default")
      (node (ref "C42") (pin "+") (pinfunction "+_+") (pintype "passive"))
      (node (ref "C43") (pin "1") (pinfunction "1_1") (pintype "passive"))
      (node (ref "D2") (pin "1") (pinfunction "1_1") (pintype "passive"))
      (node (ref "PWR_SEL") (pin "7") (pinfunction "7_7") (pintype "passive"))
      (node (ref "R43") (pin "2") (pinfunction "1.2_2") (pintype "passive"))
      (node (ref "U7") (pin "8") (pinfunction "OUT_A_8") (pintype "output"))
      (node (ref "USB_OTG1") (pin "VBUS") (pinfunction "VBUS_VBUS") (pintype "power_in"))
    )
    (net (code "5") (name "/+5V_OTG2_PWR") (class "Default")
      (node (ref "C48") (pin "+") (pinfunction "+_+") (pintype "passive"))
      (node (ref "C49") (pin "1") (pinfunction "1_1") (pintype "passive"))
      (node (ref "D3") (pin "1") (pinfunction "1_1") (pintype "passive"))
      (node (ref "PWR_SEL") (pin "5") (pinfunction "5_5") (pintype "passive"))
      (node (ref "R46") (pin "2") (pinfunction "1.2_2") (pintype "passive"))
      (node (ref "U7") (pin "5") (pinfunction "OUT_B_5") (pintype "output"))
      (node (ref "USB_OTG2") (pin "VBUS") (pinfunction "VBUS_VBUS") (pintype "power_in"))
    )
    (net (code "6") (name "/AREF") (class "Default")
      (node (ref "AREF_EN") (pin "2") (pinfunction "2_2") (pintype "passive"))
      (node (ref "CON4") (pin "8") (pinfunction "8_8") (pintype "passive"))
      (node (ref "R3") (pin "1") (pinfunction "1_1") (pintype "passive"))
      (node (ref "U4") (pin "AREF") (pinfunction "AREF_AREF") (pintype "bidirectional"))
    )
    (net (code "7") (name "/BOOT0") (class "Default")
      (node (ref "R4") (pin "1") (pinfunction "1_1") (pintype "passive"))
      (node (ref "U1") (pin "138") (pinfunction "BOOT0/VPP_138") (pintype "input"))
    )
    (net (code "8") (name "/LED") (class "Default")
      (node (ref "LED") (pin "C") (pinfunction "C_C") (pintype "passive"))
      (node (ref "U1") (pin "7") (pinfunction "PC13/RTC_AF1_7") (pintype "bidirectional"))
    )
    (net (code "9") (name "/LED100{slash}DUP") (class "Default")
      (node (ref "LAN") (pin "KY") (pinfunction "KY_KY") (pintype "passive"))
      (node (ref "R19") (pin "1") (pinfunction "1_1") (pintype "passive"))
      (node (ref "R20") (pin "1") (pinfunction "1_1") (pintype "passive"))
    )
    (net (code "10") (name "/LEDACT") (class "Default")
      (node (ref "LAN") (pin "KG") (pinfunction "KG_KG") (pintype "passive"))
      (node (ref "R21") (pin "1") (pinfunction "1_1") (pintype "passive"))
    )
    (net (code "11") (name "/PA0{slash}WKUP") (class "Default")
      (node (ref "R38") (pin "2") (pinfunction "2_2") (pintype "passive"))
      (node (ref "U1") (pin "34") (pinfunction "PA0/WKUP/USART2_CTS/USART4_TX/ETH_MII_CRS/TIM2_CH1_ETR/TIM5_CH1/TIM8_ETR/ADC123_CH0_34") (pintype "bidirectional"))
    )
    (net (code "12") (name "/PA1{slash}D8{slash}ETH_RMII_REF_CLK") (class "Default")
      (node (ref "CD1") (pin "3") (pinfunction "OUT_3") (pintype "output"))
      (node (ref "U1") (pin "35") (pinfunction "PA1/USART2_RTS/USART4_RX/ETH_RMII_REF_CLK/ETH_MII_RX_CLK/TIM5_CH2/TIM2_CH2/ADC123_IN1_35") (pintype "bidirectional"))
      (node (ref "U3") (pin "15") (pinfunction "TXC/REFCLK_15") (pintype "bidirectional"))
    )
    (net (code "13") (name "/PA2{slash}ETH_RMII_MDIO") (class "Default")
      (node (ref "R30") (pin "2") (pinfunction "2_2") (pintype "passive"))
      (node (ref "U1") (pin "36") (pinfunction "PA2/USART2_TX/TIM5_CH3/TIM9_CH1/TIM2_CH3/ETH_MDIO/ADC123_IN2_36") (pintype "bidirectional"))
      (node (ref "U3") (pin "1") (pinfunction "MDIO_1") (pintype "bidirectional"))
    )
    (net (code "14") (name "/PA3{slash}ETH_RMII_MDINT") (class "Default")
      (node (ref "R22") (pin "1") (pinfunction "1_1") (pintype "passive"))
      (node (ref "R23") (pin "1") (pinfunction "1_1") (pintype "passive"))
      (node (ref "U1") (pin "37") (pinfunction "PA3/USART2_RX/TIM5_CH4/TIM9_CH2/TIM2_CH4/OTG_HS_ULPI_D0/ETH_MII_COL/ADC123_IN3_37") (pintype "bidirectional"))
    )
    (net (code "15") (name "/PA4{slash}D10{slash}SPI1_NSS") (class "Default")
      (node (ref "CON4") (pin "3") (pinfunction "3_3") (pintype "passive"))
      (node (ref "U1") (pin "40") (pinfunction "PA4/SPI1_NSS/SPI3_NSS/USART2_CK/DCMI_HSYNC/OTG_HS_SOF/I2S3_WS/ADC12_IN4/DAC1_OUT_40") (pintype "bidirectional"))
      (node (ref "U4") (pin "D10") (pinfunction "D10_D10") (pintype "bidirectional"))
    )
    (net (code "16") (name "/PA5{slash}D13{slash}SPI1_SCK") (class "Default")
      (node (ref "CON4") (pin "6") (pinfunction "6_6") (pintype "passive"))
      (node (ref "U1") (pin "41") (pinfunction "PA5/SPI1_SCK/OTG_HS_ULPI_CK/TIM2_CH1_ETR/TIM8_CHIN/ADC12_IN5/DAC2_OUT_41") (pintype "bidirectional"))
      (node (ref "U4") (pin "D13") (pinfunction "D13_D13") (pintype "bidirectional"))
    )
    (net (code "17") (name "/PA6{slash}D12{slash}SPI1_MISO") (class "Default")
      (node (ref "CON4") (pin "5") (pinfunction "5_5") (pintype "passive"))
      (node (ref "U1") (pin "42") (pinfunction "PA6/SPI1_MISO/TIM8_BKIN/TIM13_CH1/DCMI_PIXCLK/TIM3_CH1/TIM1_BKIN/ADC12_IN6_42") (pintype "bidirectional"))
      (node (ref "U4") (pin "D12") (pinfunction "D12_D12") (pintype "bidirectional"))
    )
    (net (code "18") (name "/PA7{slash}D11{slash}ETH_RMII_CRS_DV") (class "Default")
      (node (ref "R31") (pin "1") (pinfunction "1_1") (pintype "passive"))
      (node (ref "U1") (pin "43") (pinfunction "PA7/SPI1_MOSI/TIM8_CH1N/TIM14_CH1/TIM3_CH2/ETH_MII_RX_DV/TIM1_CH1N/RMII_CRS_DV/ADC12_IN7_43") (pintype "bidirectional"))
      (node (ref "U3") (pin "9") (pinfunction "RXDV/CRSDV/PCS_LPBK_9") (pintype "bidirectional"))
    )
    (net (code "19") (name "/PA8{slash}USB_HS_VBUSON") (class "Default")
      (node (ref "RM6") (pin "1.1") (pinfunction "1_1.1") (pintype "passive"))
      (node (ref "U1") (pin "100") (pinfunction "PA8/MCO1/USART1_CK/TIM1_CH1/I2C3_SCL/OTG_FS_SOF_100") (pintype "bidirectional"))
      (node (ref "U7") (pin "4") (pinfunction "ENB_4") (pintype "input"))
    )
    (net (code "20") (name "/PA9{slash}OTG_FS_VBUS") (class "Default")
      (node (ref "R43") (pin "1") (pinfunction "1.1_1") (pintype "passive"))
      (node (ref "U1") (pin "101") (pinfunction "PA9/USART1_TX/TIM1_CH2/I2C3_SMBA/DCMI_D0/OTG_FS_VBUS_101") (pintype "bidirectional"))
    )
    (net (code "21") (name "/PA10{slash}OTG1_FS_ID") (class "Default")
      (node (ref "D2") (pin "2") (pinfunction "2_2") (pintype "passive"))
      (node (ref "U1") (pin "102") (pinfunction "PA10/USART1_RX/TIM1_CH3/OTG_FS_ID/DCMI_D1_102") (pintype "bidirectional"))
      (node (ref "USB_OTG1") (pin "ID") (pinfunction "ID_ID") (pintype "input"))
    )
    (net (code "22") (name "/PA11{slash}OTG_FS_DM") (class "Default")
      (node (ref "C39") (pin "1") (pinfunction "1_1") (pintype "passive"))
      (node (ref "R44") (pin "1") (pinfunction "1_1") (pintype "passive"))
      (node (ref "U1") (pin "103") (pinfunction "PA11/USART1_CTS/CAN1_RX/TIM1_CH4/OTG_FS_DM_103") (pintype "bidirectional"))
    )
    (net (code "23") (name "/PA12{slash}OTG_FS_DP") (class "Default")
      (node (ref "C40") (pin "1") (pinfunction "1_1") (pintype "passive"))
      (node (ref "R45") (pin "1") (pinfunction "1_1") (pintype "passive"))
      (node (ref "U1") (pin "104") (pinfunction "PA12/USART1_RTS/CAN1_TX/TIM1_ETR/OTG_FS_DP_104") (pintype "bidirectional"))
    )
    (net (code "24") (name "/PA13{slash}TMS") (class "Default")
      (node (ref "JTAG") (pin "7") (pinfunction "7_7") (pintype "passive"))
      (node (ref "RM4") (pin "3.1") (pinfunction "1_3.1") (pintype "passive"))
      (node (ref "U1") (pin "105") (pinfunction "PA13/JTMS-SWDIO_105") (pintype "bidirectional"))
    )
    (net (code "25") (name "/PA14{slash}TCK") (class "Default")
      (node (ref "JTAG") (pin "9") (pinfunction "9_9") (pintype "passive"))
      (node (ref "RM4") (pin "2.2") (pinfunction "2_2.2") (pintype "passive"))
      (node (ref "U1") (pin "109") (pinfunction "PA14/JTCK-SWCLK_109") (pintype "bidirectional"))
    )
    (net (code "26") (name "/PA15{slash}TDI") (class "Default")
      (node (ref "JTAG") (pin "5") (pinfunction "5_5") (pintype "passive"))
      (node (ref "RM4") (pin "1.1") (pinfunction "1_1.1") (pintype "passive"))
      (node (ref "U1") (pin "110") (pinfunction "PA15/JTDI/SPI3_NSS/I2S3_WS/TIM2_CH1_ETR/SPI1_NSS_110") (pintype "bidirectional"))
    )
    (net (code "27") (name "/PB0{slash}USB_FS_VBUSON") (class "Default")
      (node (ref "RM6") (pin "4.1") (pinfunction "1_4.1") (pintype "passive"))
      (node (ref "U1") (pin "46") (pinfunction "PB0/TIM3_CH3/TIM8_CH2N/OTG_HS_ULPI_D1/ETH_MII_RXD2/TIM1_CH2N/ADC12_IN8_46") (pintype "bidirectional"))
      (node (ref "U7") (pin "1") (pinfunction "ENA_1") (pintype "input"))
    )
    (net (code "28") (name "/PB1{slash}USB_FS_FAULT") (class "Default")
      (node (ref "RM6") (pin "3.1") (pinfunction "1_3.1") (pintype "passive"))
      (node (ref "U1") (pin "47") (pinfunction "PB1/TIM3_CH4/TIM8_CH3N/OTG_HS_ULPI_D2/ETH_MII_RXD3/OTG_HS_INTN/TIM1_CH3N/ADC12_IN9_47") (pintype "bidirectional"))
      (node (ref "U7") (pin "2") (pinfunction "FLAG_A_2") (pintype "open_collector"))
    )
    (net (code "29") (name "/PB2") (class "Default")
      (node (ref "R9") (pin "1") (pinfunction "1_1") (pintype "passive"))
      (node (ref "U1") (pin "48") (pinfunction "PB2/BOOT1_48") (pintype "bidirectional"))
    )
    (net (code "30") (name "/PB3{slash}TDO") (class "Default")
      (node (ref "JTAG") (pin "13") (pinfunction "13_13") (pintype "passive"))
      (node (ref "R34") (pin "1") (pinfunction "1_1") (pintype "passive"))
      (node (ref "U1") (pin "133") (pinfunction "PB3/JTDO/TRACESWO/SPI3_SCK/I2S3_CK/TIM2_CH2/SPI1_SCK_133") (pintype "bidirectional"))
    )
    (net (code "31") (name "/PB4{slash}TRST") (class "Default")
      (node (ref "JTAG") (pin "3") (pinfunction "3_3") (pintype "passive"))
      (node (ref "R-T") (pin "1") (pinfunction "1_1") (pintype "passive"))
      (node (ref "RM4") (pin "4.1") (pinfunction "1_4.1") (pintype "passive"))
      (node (ref "U1") (pin "134") (pinfunction "PB4/NJTRST/SPI3_MISO/TIM3_CH1/SPI1_MISO_134") (pintype "bidirectional"))
    )
    (net (code "32") (name "/PB5{slash}D11{slash}SPI1_MOSI") (class "Default")
      (node (ref "CON4") (pin "4") (pinfunction "4_4") (pintype "passive"))
      (node (ref "U1") (pin "135") (pinfunction "PB5/I2C1_SMBA/CAN2_RX/OTG_HS_ULPI_D7/ETH_PPS_OUT/TIM3_CH2/SPI1_MOSI/SPI3_MOSI/DCMI_D10/I2S3_SD_135") (pintype "bidirectional"))
      (node (ref "U4") (pin "D11") (pinfunction "D11_D11") (pintype "bidirectional"))
    )
    (net (code "33") (name "/PB6{slash}D1{slash}USART1_TX") (class "Default")
      (node (ref "CON3") (pin "2") (pinfunction "2_2") (pintype "passive"))
      (node (ref "U1") (pin "136") (pinfunction "PB6/I2C1_SCL/TIM4_CH1/CAN2_TX/OTG_FS_INTN/DCMI_D5/USART1_TX_136") (pintype "bidirectional"))
      (node (ref "U4") (pin "D1") (pinfunction "D1_D1") (pintype "bidirectional"))
    )
    (net (code "34") (name "/PB8{slash}I2C1_SCL") (class "Default")
      (node (ref "R35") (pin "1") (pinfunction "1_1") (pintype "passive"))
      (node (ref "U1") (pin "139") (pinfunction "PB8/TIM4_CH3/SDIO_D4/TIM10_CH1/DCMI_D6/OTG_FS_SCL/ETH_MII_TXD3/I2C1_SCL/CAN1_RX_139") (pintype "bidirectional"))
      (node (ref "UEXT") (pin "5") (pinfunction "5_5") (pintype "passive"))
    )
    (net (code "35") (name "/PB9{slash}I2C1_SDA") (class "Default")
      (node (ref "R36") (pin "1") (pinfunction "1_1") (pintype "passive"))
      (node (ref "U1") (pin "140") (pinfunction "PB9/SPI2_NSS/I2S2_WS/TIM4_CH4/TIM11_CH1/OTG_FS_SDA/SDIO_D5/DCMI_D7/I2C1_SDA/CAN1_TX_140") (pintype "bidirectional"))
      (node (ref "UEXT") (pin "6") (pinfunction "6_6") (pintype "passive"))
    )
    (net (code "36") (name "/PB10{slash}SPI2_SCK{slash}UART3_TX") (class "Default")
      (node (ref "BOOT") (pin "1") (pinfunction "1_1") (pintype "passive"))
      (node (ref "U1") (pin "69") (pinfunction "PB10/SPI2_SCK/I2S2_CK/I2C2_SCL/USART3_TX/OTG_HS_ULPI_D3/ETH_MII_RX_ER/OTG_HS_SCL/TIM2_CH3_69") (pintype "bidirectional"))
      (node (ref "UEXT") (pin "9") (pinfunction "9_9") (pintype "passive"))
    )
    (net (code "37") (name "/PB12{slash}OTG2_HS_ID") (class "Default")
      (node (ref "D3") (pin "2") (pinfunction "2_2") (pintype "passive"))
      (node (ref "U1") (pin "73") (pinfunction "PB12/SPI2_NSS/I2S2_WS/I2C2_SMBA/USART3_CK/TIM1_BKIN/CAN2_RX/OTG_HS_ULPI_D5/ETH_RMII_TXD0/ETH_MII_TXD0/OTG_HS_ID_73") (pintype "bidirectional"))
      (node (ref "USB_OTG2") (pin "ID") (pinfunction "ID_ID") (pintype "input"))
    )
    (net (code "38") (name "/PB13{slash}OTG_HS_VBUS") (class "Default")
      (node (ref "R46") (pin "1") (pinfunction "1.1_1") (pintype "passive"))
      (node (ref "U1") (pin "74") (pinfunction "PB13/SPI2_SCK/I2S2_CK/USART3_CTS/TIM1_CH1N/CAN2_TX/OTG_HS_ULPI_D6/ETH_RMII_TXD1/ETH_MII_TXD1/OTG_HS_VBUS_74") (pintype "bidirectional"))
    )
    (net (code "39") (name "/PB14{slash}OTG_HS_DM") (class "Default")
      (node (ref "C46") (pin "1") (pinfunction "1_1") (pintype "passive"))
      (node (ref "R48") (pin "1") (pinfunction "1_1") (pintype "passive"))
      (node (ref "U1") (pin "75") (pinfunction "PB14/SPI2_MISO/TIM1_CH2N/TIM12_CH1/OTG_HS_DM/USART3_RTS/TIM8_CH2N_75") (pintype "bidirectional"))
    )
    (net (code "40") (name "/PB15{slash}OTG_HS_DP") (class "Default")
      (node (ref "C45") (pin "1") (pinfunction "1_1") (pintype "passive"))
      (node (ref "R47") (pin "1") (pinfunction "1_1") (pintype "passive"))
      (node (ref "U1") (pin "76") (pinfunction "PB15/SPI2_MOSI/I2S2_SD/TIM1_CH3N/TIM8_CH3N/TIM12_CH2/OTG_HS_DP_76") (pintype "bidirectional"))
    )
    (net (code "41") (name "/PC0{slash}A0") (class "Default")
      (node (ref "CON2") (pin "1") (pinfunction "1_1") (pintype "passive"))
      (node (ref "U1") (pin "26") (pinfunction "PC0/OTG_HS_ULPI_STP/ADC123_IN10_26") (pintype "bidirectional"))
      (node (ref "U4") (pin "A0") (pinfunction "A0_A0") (pintype "bidirectional"))
    )
    (net (code "42") (name "/PC1{slash}ETH_RMII_MDC") (class "Default")
      (node (ref "U1") (pin "27") (pinfunction "PC1/ETH_MDC/ADC123_IN11_27") (pintype "bidirectional"))
      (node (ref "U3") (pin "2") (pinfunction "MDC_2") (pintype "input"))
    )
    (net (code "43") (name "/PC2{slash}SPI2_MISO") (class "Default")
      (node (ref "U1") (pin "28") (pinfunction "PC2/SPI2_MISO/OTG_HS_ULPI_DIR/ETH_MII_TXD2/ADC123_IN12_28") (pintype "bidirectional"))
      (node (ref "UEXT") (pin "7") (pinfunction "7_7") (pintype "passive"))
    )
    (net (code "44") (name "/PC3{slash}SPI2_MOSI") (class "Default")
      (node (ref "R37") (pin "1") (pinfunction "1_1") (pintype "passive"))
      (node (ref "U1") (pin "29") (pinfunction "PC3/SPI2_MOSI/I2S2_SD/OTG_HS_ULPI_NXT/ETH_MII_TX_CLK/ADC123_IN13_29") (pintype "bidirectional"))
      (node (ref "UEXT") (pin "8") (pinfunction "8_8") (pintype "passive"))
    )
    (net (code "45") (name "/PC4{slash}ETH_RMII_RXD0") (class "Default")
      (node (ref "RM3") (pin "1.1") (pinfunction "1_1.1") (pintype "passive"))
      (node (ref "U1") (pin "44") (pinfunction "PC4/ETH_RMII_RX_D0/ETH_MII_RX_D0/ADC12_IN14_44") (pintype "bidirectional"))
      (node (ref "U3") (pin "6") (pinfunction "RXD0/PHYAD4_6") (pintype "bidirectional"))
    )
    (net (code "46") (name "/PC5{slash}ETH_RMII_RXD1") (class "Default")
      (node (ref "RM3") (pin "2.1") (pinfunction "1_2.1") (pintype "passive"))
      (node (ref "U1") (pin "45") (pinfunction "PC5/ETH_RMII_RX_D1/ETH_MII_RX_D1/ADC12_IN15_45") (pintype "bidirectional"))
      (node (ref "U3") (pin "5") (pinfunction "RXD1/PHYAD3_5") (pintype "bidirectional"))
    )
    (net (code "47") (name "/PC6{slash}USART6_TX") (class "Default")
      (node (ref "U1") (pin "96") (pinfunction "PC6/SPI2_MCK/TIM8_CH1/SDIO_D6/USART6_TX/DCMI_D0/TIM3_CH1_96") (pintype "bidirectional"))
      (node (ref "UEXT") (pin "3") (pinfunction "3_3") (pintype "passive"))
    )
    (net (code "48") (name "/PC7{slash}USART6_RX") (class "Default")
      (node (ref "U1") (pin "97") (pinfunction "PC7/SPI3_MCK/TIM8_CH2/SDIO_D7/USART6_RX/DCMI_D1/TIM3_CH2_97") (pintype "bidirectional"))
      (node (ref "UEXT") (pin "4") (pinfunction "4_4") (pintype "passive"))
    )
    (net (code "49") (name "/PC8{slash}SD_D0") (class "Default")
      (node (ref "RM1") (pin "2.1") (pinfunction "1_2.1") (pintype "passive"))
      (node (ref "SD/MMC") (pin "7") (pinfunction "DAT0/DO_7") (pintype "output"))
      (node (ref "U1") (pin "98") (pinfunction "PC8/TIM8_CH3/SDIO_D0/TIM3_CH3/USART6_CK/DCMI_D2_98") (pintype "bidirectional"))
    )
    (net (code "50") (name "/PC9{slash}SD_D1") (class "Default")
      (node (ref "RM1") (pin "1.1") (pinfunction "1_1.1") (pintype "passive"))
      (node (ref "SD/MMC") (pin "8") (pinfunction "DAT1/RES_8") (pintype "bidirectional"))
      (node (ref "U1") (pin "99") (pinfunction "PC9/I2S2_CKIN/I2S3_CKIN/MCO2/TIM8_CH4/SDIO_D1/I2C3_SDA/DCMI_D3/TIM3_CH4_99") (pintype "bidirectional"))
    )
    (net (code "51") (name "/PC10{slash}SD_D2") (class "Default")
      (node (ref "RM1") (pin "4.1") (pinfunction "1_4.1") (pintype "passive"))
      (node (ref "SD/MMC") (pin "1") (pinfunction "DAT2/RES_1") (pintype "bidirectional"))
      (node (ref "U1") (pin "111") (pinfunction "PC10/SPI3_SCK/I2S3_CK/UART4_TX/SDIO_D2/DCMI_D8/USART3_TX_111") (pintype "bidirectional"))
    )
    (net (code "52") (name "/PC11{slash}SD_D3") (class "Default")
      (node (ref "R11") (pin "2") (pinfunction "2_2") (pintype "passive"))
      (node (ref "R12") (pin "1") (pinfunction "1_1") (pintype "passive"))
      (node (ref "SD/MMC") (pin "2") (pinfunction "CD/DAT3/CS_2") (pintype "input"))
      (node (ref "U1") (pin "112") (pinfunction "PC11/UART4_RX/SPI3_MISO/SDIO_D3/DCMI_D4/USART3_RX_112") (pintype "bidirectional"))
    )
    (net (code "53") (name "/PC12{slash}SD_CLK") (class "Default")
      (node (ref "SD/MMC") (pin "5") (pinfunction "CLK/SCLK_5") (pintype "input"))
      (node (ref "U1") (pin "113") (pinfunction "PC12/UART5_TX/SDIO_CK/DCMI_D9/SPI3_MOSI/I2S3_SD/USART3_CK_113") (pintype "bidirectional"))
    )
    (net (code "54") (name "/PD0") (class "Default")
      (node (ref "PD") (pin "3") (pinfunction "3_3") (pintype "passive"))
      (node (ref "U1") (pin "114") (pinfunction "PD0/FSMC_D2/CAN1_RX_114") (pintype "bidirectional"))
    )
    (net (code "55") (name "/PD1") (class "Default")
      (node (ref "PD") (pin "4") (pinfunction "4_4") (pintype "passive"))
      (node (ref "U1") (pin "115") (pinfunction "PD1/FSMC_D3/CAN1_TX_115") (pintype "bidirectional"))
    )
    (net (code "56") (name "/PD2{slash}SD_CMD") (class "Default")
      (node (ref "R49") (pin "2") (pinfunction "2_2") (pintype "passive"))
      (node (ref "RM1") (pin "3.1") (pinfunction "1_3.1") (pintype "passive"))
      (node (ref "SD/MMC") (pin "3") (pinfunction "CMD/DI_3") (pintype "input"))
      (node (ref "U1") (pin "116") (pinfunction "PD2/TIM3_ETR/UART5_RX/SDIO_CMD/DCMI_D11_116") (pintype "bidirectional"))
    )
    (net (code "57") (name "/PD3") (class "Default")
      (node (ref "PD") (pin "6") (pinfunction "6_6") (pintype "passive"))
      (node (ref "U1") (pin "117") (pinfunction "PD3/FSMC_CLK/USART2_CTS_117") (pintype "bidirectional"))
    )
    (net (code "58") (name "/PD4") (class "Default")
      (node (ref "PD") (pin "7") (pinfunction "7_7") (pintype "passive"))
      (node (ref "U1") (pin "118") (pinfunction "PD4/FSMC_NOE/USART2_RTS_118") (pintype "bidirectional"))
    )
    (net (code "59") (name "/PD5") (class "Default")
      (node (ref "PD") (pin "8") (pinfunction "8_8") (pintype "passive"))
      (node (ref "U1") (pin "119") (pinfunction "PD5/FSMC_NWE/USART2_TX_119") (pintype "bidirectional"))
    )
    (net (code "60") (name "/PD6") (class "Default")
      (node (ref "PD") (pin "9") (pinfunction "9_9") (pintype "passive"))
      (node (ref "U1") (pin "122") (pinfunction "PD6/FSMC_NWAIT/USART2_RX_122") (pintype "bidirectional"))
    )
    (net (code "61") (name "/PD7") (class "Default")
      (node (ref "PD") (pin "10") (pinfunction "10_10") (pintype "passive"))
      (node (ref "U1") (pin "123") (pinfunction "PD7/USART2_CK/FSMC_NE1/FSMC_NCE2_123") (pintype "bidirectional"))
    )
    (net (code "62") (name "/PD8") (class "Default")
      (node (ref "PD") (pin "11") (pinfunction "11_11") (pintype "passive"))
      (node (ref "U1") (pin "77") (pinfunction "PD8/FSMC_D13/USART3_TX_77") (pintype "bidirectional"))
    )
    (net (code "63") (name "/PD9") (class "Default")
      (node (ref "PD") (pin "12") (pinfunction "12_12") (pintype "passive"))
      (node (ref "U1") (pin "78") (pinfunction "PD9/FSMC_D14/USART3_RX_78") (pintype "bidirectional"))
    )
    (net (code "64") (name "/PD10") (class "Default")
      (node (ref "PD") (pin "13") (pinfunction "13_13") (pintype "passive"))
      (node (ref "U1") (pin "79") (pinfunction "PD10/FSMC_D15/USART3_CK_79") (pintype "bidirectional"))
    )
    (net (code "65") (name "/PD11") (class "Default")
      (node (ref "PD") (pin "14") (pinfunction "14_14") (pintype "passive"))
      (node (ref "U1") (pin "80") (pinfunction "PD11/FSMC_A16/USART3_CTS_80") (pintype "bidirectional"))
    )
    (net (code "66") (name "/PD12") (class "Default")
      (node (ref "PD") (pin "15") (pinfunction "15_15") (pintype "passive"))
      (node (ref "U1") (pin "81") (pinfunction "PD12/FSMC_A17/TIM4_CH1/USART3_RTS_81") (pintype "bidirectional"))
    )
    (net (code "67") (name "/PD13") (class "Default")
      (node (ref "PD") (pin "16") (pinfunction "16_16") (pintype "passive"))
      (node (ref "U1") (pin "82") (pinfunction "PD13/FSMC_A18/TIM4_CH2_82") (pintype "bidirectional"))
    )
    (net (code "68") (name "/PD14") (class "Default")
      (node (ref "PD") (pin "17") (pinfunction "17_17") (pintype "passive"))
      (node (ref "U1") (pin "85") (pinfunction "PD14/FSMC_D0/TIM4_CH3_85") (pintype "bidirectional"))
    )
    (net (code "69") (name "/PD15") (class "Default")
      (node (ref "PD") (pin "18") (pinfunction "18_18") (pintype "passive"))
      (node (ref "U1") (pin "86") (pinfunction "PD15/FSMC_D1/TIM4_CH4_86") (pintype "bidirectional"))
    )
    (net (code "70") (name "/PE0") (class "Default")
      (node (ref "PE") (pin "3") (pinfunction "3_3") (pintype "passive"))
      (node (ref "U1") (pin "141") (pinfunction "PE0/TIM4_ETR/FSMC_NBL0/DCMI_D2_141") (pintype "bidirectional"))
    )
    (net (code "71") (name "/PE1") (class "Default")
      (node (ref "PE") (pin "4") (pinfunction "4_4") (pintype "passive"))
      (node (ref "U1") (pin "142") (pinfunction "PE1/FSMC_NBL1/DCMI_D3_142") (pintype "bidirectional"))
    )
    (net (code "72") (name "/PE2{slash}D2") (class "Default")
      (node (ref "CON3") (pin "3") (pinfunction "3_3") (pintype "passive"))
      (node (ref "PE2_E") (pin "1") (pinfunction "1_1") (pintype "passive"))
      (node (ref "U1") (pin "1") (pinfunction "PE2/TRACECK/FSMC_A23/ETH_MII_TXD3_1") (pintype "bidirectional"))
      (node (ref "U4") (pin "D2") (pinfunction "D2_D2") (pintype "bidirectional"))
    )
    (net (code "73") (name "/PE3") (class "Default")
      (node (ref "PE") (pin "6") (pinfunction "6_6") (pintype "passive"))
      (node (ref "U1") (pin "2") (pinfunction "PE3/TRACED0/FSMC_A19_2") (pintype "bidirectional"))
    )
    (net (code "74") (name "/PE4{slash}D3") (class "Default")
      (node (ref "CON3") (pin "4") (pinfunction "4_4") (pintype "passive"))
      (node (ref "PE4_E") (pin "1") (pinfunction "1_1") (pintype "passive"))
      (node (ref "U1") (pin "3") (pinfunction "PE4/TRACED1/FSMC_A20/DCMI_D4_3") (pintype "bidirectional"))
      (node (ref "U4") (pin "D3") (pinfunction "D3_D3") (pintype "bidirectional"))
    )
    (net (code "75") (name "/PE5{slash}D4") (class "Default")
      (node (ref "CON3") (pin "5") (pinfunction "5_5") (pintype "passive"))
      (node (ref "PE5_E") (pin "2") (pinfunction "2_2") (pintype "passive"))
      (node (ref "U1") (pin "4") (pinfunction "PE5/TRACED2/FSMC_A21/TIM9_CH1/DCMI_D6_4") (pintype "bidirectional"))
      (node (ref "U4") (pin "D4") (pinfunction "D4_D4") (pintype "bidirectional"))
    )
    (net (code "76") (name "/PE6{slash}D5") (class "Default")
      (node (ref "CON3") (pin "6") (pinfunction "6_6") (pintype "passive"))
      (node (ref "PE6_E") (pin "1") (pinfunction "1_1") (pintype "passive"))
      (node (ref "U1") (pin "5") (pinfunction "PE6/TRACED3/FSMC_A22/TIM9_CH2/DCMI_D7_5") (pintype "bidirectional"))
      (node (ref "U4") (pin "D5") (pinfunction "D5_D5") (pintype "bidirectional"))
    )
    (net (code "77") (name "/PE7") (class "Default")
      (node (ref "PE") (pin "10") (pinfunction "10_10") (pintype "passive"))
      (node (ref "U1") (pin "58") (pinfunction "PE7/FSMC_D4/TIM1_ETR_58") (pintype "bidirectional"))
    )
    (net (code "78") (name "/PE8") (class "Default")
      (node (ref "PE") (pin "11") (pinfunction "11_11") (pintype "passive"))
      (node (ref "U1") (pin "59") (pinfunction "PE8/FSMC_D5/TIM1_CH1N_59") (pintype "bidirectional"))
    )
    (net (code "79") (name "/PE9") (class "Default")
      (node (ref "PE") (pin "12") (pinfunction "12_12") (pintype "passive"))
      (node (ref "U1") (pin "60") (pinfunction "PE9/FSMC_D6/TIM1_CH1_60") (pintype "bidirectional"))
    )
    (net (code "80") (name "/PE10") (class "Default")
      (node (ref "PE") (pin "13") (pinfunction "13_13") (pintype "passive"))
      (node (ref "U1") (pin "63") (pinfunction "PE10/FSMC_D7/TIM1_CH2N_63") (pintype "bidirectional"))
    )
    (net (code "81") (name "/PE11") (class "Default")
      (node (ref "PE") (pin "14") (pinfunction "14_14") (pintype "passive"))
      (node (ref "U1") (pin "64") (pinfunction "PE11/FSMC_D8/TIM1_CH2_64") (pintype "bidirectional"))
    )
    (net (code "82") (name "/PE12") (class "Default")
      (node (ref "PE") (pin "15") (pinfunction "15_15") (pintype "passive"))
      (node (ref "U1") (pin "65") (pinfunction "PE12/FSMC_D9/TIM1_CH3N_65") (pintype "bidirectional"))
    )
    (net (code "83") (name "/PE13") (class "Default")
      (node (ref "PE") (pin "16") (pinfunction "16_16") (pintype "passive"))
      (node (ref "U1") (pin "66") (pinfunction "PE13/FSMC_D10/TIM1_CH3_66") (pintype "bidirectional"))
    )
    (net (code "84") (name "/PE14") (class "Default")
      (node (ref "PE") (pin "17") (pinfunction "17_17") (pintype "passive"))
      (node (ref "U1") (pin "67") (pinfunction "PE14/FSMC_D11/TIM1_CH4_67") (pintype "bidirectional"))
    )
    (net (code "85") (name "/PE15") (class "Default")
      (node (ref "PE") (pin "18") (pinfunction "18_18") (pintype "passive"))
      (node (ref "U1") (pin "68") (pinfunction "PE15/FSMC_D12/TIM1_BKIN_68") (pintype "bidirectional"))
    )
    (net (code "86") (name "/PF0") (class "Default")
      (node (ref "PF") (pin "3") (pinfunction "3_3") (pintype "passive"))
      (node (ref "U1") (pin "10") (pinfunction "PF0/FSMC_A0/I2C2_SDA_10") (pintype "bidirectional"))
    )
    (net (code "87") (name "/PF1") (class "Default")
      (node (ref "PF") (pin "4") (pinfunction "4_4") (pintype "passive"))
      (node (ref "U1") (pin "11") (pinfunction "PF1/FSMC_A1/I2C2_SCL_11") (pintype "bidirectional"))
    )
    (net (code "88") (name "/PF2") (class "Default")
      (node (ref "PF") (pin "5") (pinfunction "5_5") (pintype "passive"))
      (node (ref "U1") (pin "12") (pinfunction "PF2/FSMC_A2/I2C2_SMBA_12") (pintype "bidirectional"))
    )
    (net (code "89") (name "/PF3") (class "Default")
      (node (ref "PF") (pin "6") (pinfunction "6_6") (pintype "passive"))
      (node (ref "U1") (pin "13") (pinfunction "PF3/FSMC_A3/ADC3_IN9_13") (pintype "bidirectional"))
    )
    (net (code "90") (name "/PF4") (class "Default")
      (node (ref "PF") (pin "7") (pinfunction "7_7") (pintype "passive"))
      (node (ref "U1") (pin "14") (pinfunction "PF4/FSMC_A4/ADC3_IN14_14") (pintype "bidirectional"))
    )
    (net (code "91") (name "/PF5") (class "Default")
      (node (ref "PF") (pin "8") (pinfunction "8_8") (pintype "passive"))
      (node (ref "U1") (pin "15") (pinfunction "PF5/FSMC_A5/ADC3_IN15_15") (pintype "bidirectional"))
    )
    (net (code "92") (name "/PF6{slash}A1") (class "Default")
      (node (ref "CON2") (pin "2") (pinfunction "2_2") (pintype "passive"))
      (node (ref "PF6_E") (pin "1") (pinfunction "1_1") (pintype "passive"))
      (node (ref "U1") (pin "18") (pinfunction "PF6/TIM10_CH1/FSMC_NIORD/ADC3_IN4_18") (pintype "bidirectional"))
      (node (ref "U4") (pin "A1") (pinfunction "A1_A1") (pintype "bidirectional"))
    )
    (net (code "93") (name "/PF7{slash}A2") (class "Default")
      (node (ref "CON2") (pin "3") (pinfunction "3_3") (pintype "passive"))
      (node (ref "PF7_E") (pin "2") (pinfunction "2_2") (pintype "passive"))
      (node (ref "U1") (pin "19") (pinfunction "PF7/TIM11_CH1/FSMC_NREG/ADC3_IN5_19") (pintype "bidirectional"))
      (node (ref "U4") (pin "A2") (pinfunction "A2_A2") (pintype "bidirectional"))
    )
    (net (code "94") (name "/PF9{slash}A4") (class "Default")
      (node (ref "CON2") (pin "5") (pinfunction "5_5") (pintype "passive"))
      (node (ref "PF9_E") (pin "2") (pinfunction "2_2") (pintype "passive"))
      (node (ref "R42") (pin "1") (pinfunction "1_1") (pintype "passive"))
      (node (ref "U1") (pin "21") (pinfunction "PF9/TIM14_CH1/FSMC_CD/ADC3_IN7_21") (pintype "bidirectional"))
      (node (ref "U4") (pin "A4") (pinfunction "A4_A4") (pintype "bidirectional"))
    )
    (net (code "95") (name "/PF10{slash}A5") (class "Default")
      (node (ref "CON2") (pin "6") (pinfunction "6_6") (pintype "passive"))
      (node (ref "PF10_E") (pin "1") (pinfunction "1_1") (pintype "passive"))
      (node (ref "R41") (pin "1") (pinfunction "1_1") (pintype "passive"))
      (node (ref "U1") (pin "22") (pinfunction "PF10/FSMC_INTR/ADC3_IN8_22") (pintype "bidirectional"))
      (node (ref "U4") (pin "A5") (pinfunction "A5_A5") (pintype "bidirectional"))
    )
    (net (code "96") (name "/PF11{slash}USB_HS_FAULT") (class "Default")
      (node (ref "PF11_E") (pin "2") (pinfunction "2_2") (pintype "passive"))
      (node (ref "RM6") (pin "2.1") (pinfunction "1_2.1") (pintype "passive"))
      (node (ref "U1") (pin "49") (pinfunction "PF11/DCMI_12_49") (pintype "bidirectional"))
      (node (ref "U7") (pin "3") (pinfunction "FLAG_B_3") (pintype "open_collector"))
    )
    (net (code "97") (name "/PF12") (class "Default")
      (node (ref "PF") (pin "15") (pinfunction "15_15") (pintype "passive"))
      (node (ref "U1") (pin "50") (pinfunction "PF12/FSMC_A6_50") (pintype "bidirectional"))
    )
    (net (code "98") (name "/PF13") (class "Default")
      (node (ref "PF") (pin "16") (pinfunction "16_16") (pintype "passive"))
      (node (ref "U1") (pin "53") (pinfunction "PF13/FSMC_A7_53") (pintype "bidirectional"))
    )
    (net (code "99") (name "/PF14") (class "Default")
      (node (ref "PF") (pin "17") (pinfunction "17_17") (pintype "passive"))
      (node (ref "U1") (pin "54") (pinfunction "PF14/FSMC_A8_54") (pintype "bidirectional"))
    )
    (net (code "100") (name "/PF15") (class "Default")
      (node (ref "PF") (pin "18") (pinfunction "18_18") (pintype "passive"))
      (node (ref "U1") (pin "55") (pinfunction "PF15/FSMC_A9_55") (pintype "bidirectional"))
    )
    (net (code "101") (name "/PG0") (class "Default")
      (node (ref "PG") (pin "3") (pinfunction "3_3") (pintype "passive"))
      (node (ref "U1") (pin "56") (pinfunction "PG0/FSMC_A10_56") (pintype "bidirectional"))
    )
    (net (code "102") (name "/PG1") (class "Default")
      (node (ref "PG") (pin "4") (pinfunction "4_4") (pintype "passive"))
      (node (ref "U1") (pin "57") (pinfunction "PG1/FSMC_A11_57") (pintype "bidirectional"))
    )
    (net (code "103") (name "/PG2") (class "Default")
      (node (ref "PG") (pin "5") (pinfunction "5_5") (pintype "passive"))
      (node (ref "U1") (pin "87") (pinfunction "PG2/FSMC_A12_87") (pintype "bidirectional"))
    )
    (net (code "104") (name "/PG3") (class "Default")
      (node (ref "PG") (pin "6") (pinfunction "6_6") (pintype "passive"))
      (node (ref "U1") (pin "88") (pinfunction "PG3/FSMC_A13_88") (pintype "bidirectional"))
    )
    (net (code "105") (name "/PG4") (class "Default")
      (node (ref "PG") (pin "7") (pinfunction "7_7") (pintype "passive"))
      (node (ref "U1") (pin "89") (pinfunction "PG4/FSMC_A14_89") (pintype "bidirectional"))
    )
    (net (code "106") (name "/PG5") (class "Default")
      (node (ref "PG") (pin "8") (pinfunction "8_8") (pintype "passive"))
      (node (ref "U1") (pin "90") (pinfunction "PG5/FSMC_A15_90") (pintype "bidirectional"))
    )
    (net (code "107") (name "/PG6") (class "Default")
      (node (ref "PG") (pin "9") (pinfunction "9_9") (pintype "passive"))
      (node (ref "U1") (pin "91") (pinfunction "PG6/FSMC_INT2_91") (pintype "bidirectional"))
    )
    (net (code "108") (name "/PG7{slash}D6") (class "Default")
      (node (ref "CON3") (pin "7") (pinfunction "7_7") (pintype "passive"))
      (node (ref "PG7_E") (pin "2") (pinfunction "2_2") (pintype "passive"))
      (node (ref "U1") (pin "92") (pinfunction "PG7/FSMC_INT3/USART6_CK_92") (pintype "bidirectional"))
      (node (ref "U4") (pin "D6") (pinfunction "D6_D6") (pintype "bidirectional"))
    )
    (net (code "109") (name "/PG8{slash}D7") (class "Default")
      (node (ref "CON3") (pin "8") (pinfunction "8_8") (pintype "passive"))
      (node (ref "PG8_E") (pin "1") (pinfunction "1_1") (pintype "passive"))
      (node (ref "U1") (pin "93") (pinfunction "PG8/USART6_RTS/ETH_PPS_OUT_93") (pintype "bidirectional"))
      (node (ref "U4") (pin "D7") (pinfunction "D7_D7") (pintype "bidirectional"))
    )
    (net (code "110") (name "/PG9") (class "Default")
      (node (ref "PG") (pin "12") (pinfunction "12_12") (pintype "passive"))
      (node (ref "U1") (pin "124") (pinfunction "PG9/USART6_RX/FSMC_NE2/FSMC_NCE3_124") (pintype "bidirectional"))
    )
    (net (code "111") (name "/PG10{slash}UEXT_CS") (class "Default")
      (node (ref "R50") (pin "2") (pinfunction "2_2") (pintype "passive"))
      (node (ref "U1") (pin "125") (pinfunction "PG10/FSMC_NCE4_1/FSMC_NE3_125") (pintype "bidirectional"))
      (node (ref "UEXT") (pin "10") (pinfunction "10_10") (pintype "passive"))
    )
    (net (code "112") (name "/PG11{slash}ETH_RMII_TX_EN") (class "Default")
      (node (ref "R51") (pin "1") (pinfunction "1_1") (pintype "passive"))
      (node (ref "U1") (pin "126") (pinfunction "PG11/FSMC_NCE4_2/ETH_MII_TX_EN_126") (pintype "bidirectional"))
      (node (ref "U3") (pin "16") (pinfunction "TXEN_16") (pintype "input"))
    )
    (net (code "113") (name "/PG12{slash}D8") (class "Default")
      (node (ref "CON4") (pin "1") (pinfunction "1_1") (pintype "passive"))
      (node (ref "PG12_E") (pin "1") (pinfunction "1_1") (pintype "passive"))
      (node (ref "U1") (pin "127") (pinfunction "PG12/FSMC_NE4/USART6_RTS_127") (pintype "bidirectional"))
      (node (ref "U4") (pin "D8") (pinfunction "D8_D8") (pintype "bidirectional"))
    )
    (net (code "114") (name "/PG13{slash}ETH_RMII_TXD0") (class "Default")
      (node (ref "R52") (pin "1") (pinfunction "1_1") (pintype "passive"))
      (node (ref "U1") (pin "128") (pinfunction "PG13/FSMC_A24/USART6_CTS/ETH_MII_TXD0/ETH_RMII_TXD0_128") (pintype "bidirectional"))
      (node (ref "U3") (pin "17") (pinfunction "TXD0_17") (pintype "input"))
    )
    (net (code "115") (name "/PG14{slash}ETH_RMII_TXD1") (class "Default")
      (node (ref "R53") (pin "2") (pinfunction "2_2") (pintype "passive"))
      (node (ref "U1") (pin "129") (pinfunction "PG14/FSMC_A25/USART6_TX/ETH_MII_TXD1/ETH_RMII_TXD1_129") (pintype "bidirectional"))
      (node (ref "U3") (pin "18") (pinfunction "TXD1_18") (pintype "input"))
    )
    (net (code "116") (name "/PG15{slash}D9") (class "Default")
      (node (ref "CON4") (pin "2") (pinfunction "2_2") (pintype "passive"))
      (node (ref "PG15_E") (pin "2") (pinfunction "2_2") (pintype "passive"))
      (node (ref "U1") (pin "132") (pinfunction "PG15/USART6_CTS/DCMI_D13_132") (pintype "bidirectional"))
      (node (ref "U4") (pin "D9") (pinfunction "D9_D9") (pintype "bidirectional"))
    )
    (net (code "117") (name "/PHY_RSTN") (class "Default")
      (node (ref "R28") (pin "2") (pinfunction "2_2") (pintype "passive"))
      (node (ref "R29") (pin "1") (pinfunction "1.1_1") (pintype "passive"))
      (node (ref "U3") (pin "48") (pinfunction "RST#_48") (pintype "input"))
    )
    (net (code "118") (name "/PHY_VDD_PLL") (class "Default")
      (node (ref "C35") (pin "1") (pinfunction "1_1") (pintype "passive"))
      (node (ref "C36") (pin "1") (pinfunction "1_1") (pintype "passive"))
      (node (ref "FB1") (pin "1") (pinfunction "1_1") (pintype "passive"))
      (node (ref "FB2") (pin "1") (pinfunction "1_1") (pintype "passive"))
      (node (ref "U3") (pin "47") (pinfunction "VDDPLL_47") (pintype "power_in"))
    )
    (net (code "119") (name "/RB7{slash}D0{slash}USART1_RX") (class "Default")
      (node (ref "CON3") (pin "1") (pinfunction "1_1") (pintype "passive"))
      (node (ref "U1") (pin "137") (pinfunction "PB7/I2C1_SDA/FSMC_NL/DCMI_VSYNC/USART1_RX/TIM4_CH2_137") (pintype "bidirectional"))
      (node (ref "U4") (pin "D0") (pinfunction "D0_D0") (pintype "bidirectional"))
    )
    (net (code "120") (name "/RB11{slash}UART3_RX") (class "Default")
      (node (ref "BOOT") (pin "2") (pinfunction "2_2") (pintype "passive"))
      (node (ref "U1") (pin "70") (pinfunction "PB11/I2C2_SDA/USART3_RX/OTG_HS_ULPI_D4/ETH_RMII_TX_EN/ETH_MII_TX_EN/OTG_HS_SDA/TIM2_CH4_70") (pintype "bidirectional"))
    )
    (net (code "121") (name "/RF8{slash}A3") (class "Default")
      (node (ref "CON2") (pin "4") (pinfunction "4_4") (pintype "passive"))
      (node (ref "PF8_E") (pin "1") (pinfunction "1_1") (pintype "passive"))
      (node (ref "U1") (pin "20") (pinfunction "PF8/TIM13_CH1/FSMC_NIOWR/ADC3_IN6_20") (pintype "bidirectional"))
      (node (ref "U4") (pin "A3") (pinfunction "A3_A3") (pintype "bidirectional"))
    )
    (net (code "122") (name "/RST") (class "Default")
      (node (ref "CON1") (pin "1") (pinfunction "1_1") (pintype "passive"))
      (node (ref "JTAG") (pin "15") (pinfunction "15_15") (pintype "passive"))
      (node (ref "R-T") (pin "2") (pinfunction "2_2") (pintype "passive"))
      (node (ref "R29") (pin "2") (pinfunction "1.2_2") (pintype "passive"))
      (node (ref "R6") (pin "1") (pinfunction "1_1") (pintype "passive"))
      (node (ref "U1") (pin "25") (pinfunction "NRST_25") (pintype "power_in"))
      (node (ref "U4") (pin "RST") (pinfunction "RST_RST") (pintype "bidirectional"))
    )
    (net (code "123") (name "/USB_OTG1_D+") (class "Default")
      (node (ref "U5") (pin "3") (pinfunction "3_3") (pintype "bidirectional"))
      (node (ref "USB_OTG1") (pin "D+") (pinfunction "D+_D+") (pintype "input"))
    )
    (net (code "124") (name "/USB_OTG1_D-") (class "Default")
      (node (ref "U5") (pin "1") (pinfunction "1_1") (pintype "bidirectional"))
      (node (ref "USB_OTG1") (pin "D-") (pinfunction "D-_D-") (pintype "input"))
    )
    (net (code "125") (name "/USB_OTG2_D+") (class "Default")
      (node (ref "U6") (pin "3") (pinfunction "3_3") (pintype "bidirectional"))
      (node (ref "USB_OTG2") (pin "D+") (pinfunction "D+_D+") (pintype "input"))
    )
    (net (code "126") (name "/USB_OTG2_D-") (class "Default")
      (node (ref "U6") (pin "1") (pinfunction "1_1") (pintype "bidirectional"))
      (node (ref "USB_OTG2") (pin "D-") (pinfunction "D-_D-") (pintype "input"))
    )
    (net (code "127") (name "/VBAT") (class "Default")
      (node (ref "D1") (pin "3") (pinfunction "K_3") (pintype "passive"))
      (node (ref "U1") (pin "6") (pinfunction "VBAT_6") (pintype "power_in"))
    )
    (net (code "128") (name "2.5V") (class "Default")
      (node (ref "C26") (pin "1") (pinfunction "1_1") (pintype "passive"))
      (node (ref "C28") (pin "1") (pinfunction "1_1") (pintype "passive"))
      (node (ref "C30") (pin "2") (pinfunction "2_2") (pintype "passive"))
      (node (ref "C31") (pin "2") (pinfunction "2_2") (pintype "passive"))
      (node (ref "FB1") (pin "2") (pinfunction "2_2") (pintype "passive"))
      (node (ref "LAN") (pin "3") (pinfunction "COM_3") (pintype "bidirectional"))
      (node (ref "R13") (pin "2") (pinfunction "2_2") (pintype "passive"))
      (node (ref "R14") (pin "2") (pinfunction "2_2") (pintype "passive"))
      (node (ref "R15") (pin "2") (pinfunction "2_2") (pintype "passive"))
      (node (ref "R16") (pin "2") (pinfunction "2_2") (pintype "passive"))
      (node (ref "R17") (pin "2") (pinfunction "2_2") (pintype "passive"))
      (node (ref "U3") (pin "31") (pinfunction "VDDRX_31") (pintype "power_in"))
      (node (ref "U3") (pin "38") (pinfunction "VDDRCV_38") (pintype "power_in"))
      (node (ref "U3") (pin "42") (pinfunction "VDDTX_42") (pintype "power_in"))
    )
    (net (code "129") (name "3.3V") (class "Default")
      (node (ref "3.3V_E") (pin "2") (pinfunction "2_2") (pintype "passive"))
      (node (ref "B0_1/B0_0") (pin "1") (pinfunction "1_1") (pintype "passive"))
      (node (ref "B1_1/B1_0") (pin "1") (pinfunction "1_1") (pintype "passive"))
      (node (ref "BOOT") (pin "4") (pinfunction "4_4") (pintype "passive"))
      (node (ref "C1") (pin "2") (pinfunction "2_2") (pintype "passive"))
      (node (ref "C10") (pin "2") (pinfunction "2_2") (pintype "passive"))
      (node (ref "C11") (pin "2") (pinfunction "2_2") (pintype "passive"))
      (node (ref "C12") (pin "2") (pinfunction "2_2") (pintype "passive"))
      (node (ref "C13") (pin "2") (pinfunction "2_2") (pintype "passive"))
      (node (ref "C2") (pin "2") (pinfunction "2_2") (pintype "passive"))
      (node (ref "C29") (pin "1") (pinfunction "1_1") (pintype "passive"))
      (node (ref "C34") (pin "1") (pinfunction "1_1") (pintype "passive"))
      (node (ref "C37") (pin "2") (pinfunction "2_2") (pintype "passive"))
      (node (ref "C38") (pin "2") (pinfunction "2_2") (pintype "passive"))
      (node (ref "C4") (pin "2") (pinfunction "2_2") (pintype "passive"))
      (node (ref "C41") (pin "2") (pinfunction "2_2") (pintype "passive"))
      (node (ref "C47") (pin "2") (pinfunction "2_2") (pintype "passive"))
      (node (ref "C5") (pin "2") (pinfunction "2_2") (pintype "passive"))
      (node (ref "C6") (pin "2") (pinfunction "2_2") (pintype "passive"))
      (node (ref "C7") (pin "2") (pinfunction "2_2") (pintype "passive"))
      (node (ref "C8") (pin "2") (pinfunction "2_2") (pintype "passive"))
      (node (ref "C9") (pin "2") (pinfunction "2_2") (pintype "passive"))
      (node (ref "CD1") (pin "4") (pinfunction "VDD_4") (pintype "power_in"))
      (node (ref "CON1") (pin "2") (pinfunction "2_2") (pintype "passive"))
      (node (ref "D1") (pin "1") (pinfunction "A1_1") (pintype "passive"))
      (node (ref "JTAG") (pin "1") (pinfunction "1_1") (pintype "passive"))
      (node (ref "JTAG") (pin "2") (pinfunction "2_2") (pintype "passive"))
      (node (ref "L1") (pin "1") (pinfunction "1_1") (pintype "passive"))
      (node (ref "L2") (pin "1") (pinfunction "1_1") (pintype "passive"))
      (node (ref "LAN") (pin "AG") (pinfunction "AG_AG") (pintype "passive"))
      (node (ref "LAN") (pin "AY") (pinfunction "AY_AY") (pintype "passive"))
      (node (ref "PD") (pin "1") (pinfunction "1_1") (pintype "passive"))
      (node (ref "PE") (pin "1") (pinfunction "1_1") (pintype "passive"))
      (node (ref "PF") (pin "1") (pinfunction "1_1") (pintype "passive"))
      (node (ref "PG") (pin "1") (pinfunction "1_1") (pintype "passive"))
      (node (ref "R1") (pin "2") (pinfunction "1.2_2") (pintype "passive"))
      (node (ref "R11") (pin "1") (pinfunction "1_1") (pintype "passive"))
      (node (ref "R18") (pin "1") (pinfunction "1_1") (pintype "passive"))
      (node (ref "R23") (pin "2") (pinfunction "2_2") (pintype "passive"))
      (node (ref "R27") (pin "1") (pinfunction "1_1") (pintype "passive"))
      (node (ref "R28") (pin "1") (pinfunction "1_1") (pintype "passive"))
      (node (ref "R30") (pin "1") (pinfunction "1_1") (pintype "passive"))
      (node (ref "R32") (pin "1") (pinfunction "1_1") (pintype "passive"))
      (node (ref "R33") (pin "2") (pinfunction "2_2") (pintype "passive"))
      (node (ref "R34") (pin "2") (pinfunction "2_2") (pintype "passive"))
      (node (ref "R35") (pin "2") (pinfunction "2_2") (pintype "passive"))
      (node (ref "R36") (pin "2") (pinfunction "2_2") (pintype "passive"))
      (node (ref "R37") (pin "2") (pinfunction "2_2") (pintype "passive"))
      (node (ref "R40") (pin "2") (pinfunction "2_2") (pintype "passive"))
      (node (ref "R41") (pin "2") (pinfunction "2_2") (pintype "passive"))
      (node (ref "R42") (pin "2") (pinfunction "2_2") (pintype "passive"))
      (node (ref "R5") (pin "2") (pinfunction "2_2") (pintype "passive"))
      (node (ref "R60") (pin "1") (pinfunction "1_1") (pintype "passive"))
      (node (ref "RM1") (pin "1.2") (pinfunction "2_1.2") (pintype "passive"))
      (node (ref "RM1") (pin "2.2") (pinfunction "2_2.2") (pintype "passive"))
      (node (ref "RM1") (pin "3.2") (pinfunction "2_3.2") (pintype "passive"))
      (node (ref "RM1") (pin "4.2") (pinfunction "2_4.2") (pintype "passive"))
      (node (ref "RM2") (pin "3.1") (pinfunction "1_3.1") (pintype "passive"))
      (node (ref "RM4") (pin "1.2") (pinfunction "2_1.2") (pintype "passive"))
      (node (ref "RM4") (pin "3.2") (pinfunction "2_3.2") (pintype "passive"))
      (node (ref "RM4") (pin "4.2") (pinfunction "2_4.2") (pintype "passive"))
      (node (ref "RM6") (pin "2.2") (pinfunction "2_2.2") (pintype "passive"))
      (node (ref "RM6") (pin "3.2") (pinfunction "2_3.2") (pintype "passive"))
      (node (ref "U1") (pin "108") (pinfunction "VDD_2_108") (pintype "power_in"))
      (node (ref "U1") (pin "121") (pinfunction "VDD_10_121") (pintype "power_in"))
      (node (ref "U1") (pin "131") (pinfunction "VDD_11_131") (pintype "power_in"))
      (node (ref "U1") (pin "144") (pinfunction "VDD_SA_144") (pintype "power_in"))
      (node (ref "U1") (pin "17") (pinfunction "VDD_5_17") (pintype "power_in"))
      (node (ref "U1") (pin "30") (pinfunction "VDD_12_30") (pintype "power_in"))
      (node (ref "U1") (pin "39") (pinfunction "VDD_4_39") (pintype "power_in"))
      (node (ref "U1") (pin "52") (pinfunction "VDD_6_52") (pintype "power_in"))
      (node (ref "U1") (pin "62") (pinfunction "VDD_7_62") (pintype "power_in"))
      (node (ref "U1") (pin "72") (pinfunction "VDD_1_72") (pintype "power_in"))
      (node (ref "U1") (pin "84") (pinfunction "VDD_8_84") (pintype "power_in"))
      (node (ref "U1") (pin "95") (pinfunction "VDD_9_95") (pintype "power_in"))
      (node (ref "U2") (pin "2") (pinfunction "VCC_2") (pintype "power_in"))
      (node (ref "U3") (pin "24") (pinfunction "VDDIO2_24") (pintype "power_in"))
      (node (ref "U3") (pin "7") (pinfunction "VDDIO1_7") (pintype "power_in"))
      (node (ref "U4") (pin "3V3") (pinfunction "3V3_3V3") (pintype "bidirectional"))
      (node (ref "U5") (pin "5") (pinfunction "5_5") (pintype "power_in"))
      (node (ref "U6") (pin "5") (pinfunction "5_5") (pintype "power_in"))
      (node (ref "UEXT") (pin "1") (pinfunction "1_1") (pintype "passive"))
      (node (ref "WKUP") (pin "P$1") (pinfunction "0_P$1") (pintype "passive"))
    )
    (net (code "130") (name "3.3V_A") (class "Default")
      (node (ref "AREF_EN") (pin "1") (pinfunction "1_1") (pintype "passive"))
      (node (ref "C16") (pin "1") (pinfunction "1_1") (pintype "passive"))
      (node (ref "C17") (pin "2") (pinfunction "2_2") (pintype "passive"))
      (node (ref "L1") (pin "2") (pinfunction "2_2") (pintype "passive"))
      (node (ref "U1") (pin "33") (pinfunction "VDDA_33") (pintype "power_in"))
    )
    (net (code "131") (name "AGND") (class "Default")
      (node (ref "AGND_E") (pin "1") (pinfunction "1_1") (pintype "passive"))
      (node (ref "C16") (pin "2") (pinfunction "2_2") (pintype "passive"))
      (node (ref "C17") (pin "1") (pinfunction "1_1") (pintype "passive"))
      (node (ref "C18") (pin "1") (pinfunction "1_1") (pintype "passive"))
      (node (ref "CON4") (pin "7") (pinfunction "7_7") (pintype "passive"))
      (node (ref "U1") (pin "31") (pinfunction "VSSA_31") (pintype "power_in"))
      (node (ref "U4") (pin "GND@2") (pinfunction "GND_GND@2") (pintype "bidirectional"))
    )
    (net (code "132") (name "GND") (class "Default")
      (node (ref "3V_BAT") (pin "2") (pinfunction "2_2") (pintype "passive"))
      (node (ref "AGND_E") (pin "2") (pinfunction "2_2") (pintype "passive"))
      (node (ref "B0_1/B0_0") (pin "3") (pinfunction "3_3") (pintype "passive"))
      (node (ref "B1_1/B1_0") (pin "3") (pinfunction "3_3") (pintype "passive"))
      (node (ref "BOOT") (pin "3") (pinfunction "3_3") (pintype "passive"))
      (node (ref "C1") (pin "1") (pinfunction "1_1") (pintype "passive"))
      (node (ref "C10") (pin "1") (pinfunction "1_1") (pintype "passive"))
      (node (ref "C11") (pin "1") (pinfunction "1_1") (pintype "passive"))
      (node (ref "C12") (pin "1") (pinfunction "1_1") (pintype "passive"))
      (node (ref "C13") (pin "1") (pinfunction "1_1") (pintype "passive"))
      (node (ref "C14") (pin "1") (pinfunction "1_1") (pintype "passive"))
      (node (ref "C15") (pin "1") (pinfunction "1_1") (pintype "passive"))
      (node (ref "C19") (pin "1") (pinfunction "1_1") (pintype "passive"))
      (node (ref "C2") (pin "1") (pinfunction "1_1") (pintype "passive"))
      (node (ref "C20") (pin "2") (pinfunction "2_2") (pintype "passive"))
      (node (ref "C21") (pin "2") (pinfunction "2_2") (pintype "passive"))
      (node (ref "C22") (pin "2") (pinfunction "2_2") (pintype "passive"))
      (node (ref "C23") (pin "2") (pinfunction "2_2") (pintype "passive"))
      (node (ref "C24") (pin "2") (pinfunction "2_2") (pintype "passive"))
      (node (ref "C25") (pin "2") (pinfunction "2_2") (pintype "passive"))
      (node (ref "C26") (pin "2") (pinfunction "2_2") (pintype "passive"))
      (node (ref "C27") (pin "1") (pinfunction "1_1") (pintype "passive"))
      (node (ref "C28") (pin "2") (pinfunction "2_2") (pintype "passive"))
      (node (ref "C29") (pin "2") (pinfunction "2_2") (pintype "passive"))
      (node (ref "C3") (pin "1") (pinfunction "1_1") (pintype "passive"))
      (node (ref "C30") (pin "1") (pinfunction "1_1") (pintype "passive"))
      (node (ref "C31") (pin "1") (pinfunction "1_1") (pintype "passive"))
      (node (ref "C32") (pin "2") (pinfunction "2_2") (pintype "passive"))
      (node (ref "C33") (pin "2") (pinfunction "2_2") (pintype "passive"))
      (node (ref "C34") (pin "2") (pinfunction "2_2") (pintype "passive"))
      (node (ref "C35") (pin "2") (pinfunction "2_2") (pintype "passive"))
      (node (ref "C36") (pin "2") (pinfunction "2_2") (pintype "passive"))
      (node (ref "C37") (pin "1") (pinfunction "1_1") (pintype "passive"))
      (node (ref "C39") (pin "2") (pinfunction "2_2") (pintype "passive"))
      (node (ref "C4") (pin "1") (pinfunction "1_1") (pintype "passive"))
      (node (ref "C40") (pin "2") (pinfunction "2_2") (pintype "passive"))
      (node (ref "C41") (pin "1") (pinfunction "1_1") (pintype "passive"))
      (node (ref "C42") (pin "-") (pinfunction "-_-") (pintype "passive"))
      (node (ref "C43") (pin "2") (pinfunction "2_2") (pintype "passive"))
      (node (ref "C44") (pin "2") (pinfunction "2_2") (pintype "passive"))
      (node (ref "C45") (pin "2") (pinfunction "2_2") (pintype "passive"))
      (node (ref "C46") (pin "2") (pinfunction "2_2") (pintype "passive"))
      (node (ref "C47") (pin "1") (pinfunction "1_1") (pintype "passive"))
      (node (ref "C48") (pin "-") (pinfunction "-_-") (pintype "passive"))
      (node (ref "C49") (pin "2") (pinfunction "2_2") (pintype "passive"))
      (node (ref "C5") (pin "1") (pinfunction "1_1") (pintype "passive"))
      (node (ref "C50") (pin "-") (pinfunction "-_-") (pintype "passive"))
      (node (ref "C51") (pin "2") (pinfunction "2_2") (pintype "passive"))
      (node (ref "C54") (pin "2") (pinfunction "2_2") (pintype "passive"))
      (node (ref "C55") (pin "2") (pinfunction "2_2") (pintype "passive"))
      (node (ref "C56") (pin "-") (pinfunction "-_-") (pintype "passive"))
      (node (ref "C57") (pin "2") (pinfunction "2_2") (pintype "passive"))
      (node (ref "C59") (pin "2") (pinfunction "2_2") (pintype "passive"))
      (node (ref "C6") (pin "1") (pinfunction "1_1") (pintype "passive"))
      (node (ref "C60") (pin "2") (pinfunction "2_2") (pintype "passive"))
      (node (ref "C61") (pin "-") (pinfunction "-_-") (pintype "passive"))
      (node (ref "C62") (pin "2") (pinfunction "2_2") (pintype "passive"))
      (node (ref "C7") (pin "1") (pinfunction "1_1") (pintype "passive"))
      (node (ref "C8") (pin "1") (pinfunction "1_1") (pintype "passive"))
      (node (ref "C9") (pin "1") (pinfunction "1_1") (pintype "passive"))
      (node (ref "CD1") (pin "2") (pinfunction "VSS_2") (pintype "power_in"))
      (node (ref "CON1") (pin "4") (pinfunction "4_4") (pintype "passive"))
      (node (ref "CON1") (pin "5") (pinfunction "5_5") (pintype "passive"))
      (node (ref "D2") (pin "3") (pinfunction "3_3") (pintype "passive"))
      (node (ref "D3") (pin "3") (pinfunction "3_3") (pintype "passive"))
      (node (ref "D4") (pin "A") (pinfunction "A_A") (pintype "passive"))
      (node (ref "GND_PIN") (pin "P$1") (pinfunction "PP_P$1") (pintype "passive"))
      (node (ref "JTAG") (pin "10") (pinfunction "10_10") (pintype "passive"))
      (node (ref "JTAG") (pin "12") (pinfunction "12_12") (pintype "passive"))
      (node (ref "JTAG") (pin "14") (pinfunction "14_14") (pintype "passive"))
      (node (ref "JTAG") (pin "16") (pinfunction "16_16") (pintype "passive"))
      (node (ref "JTAG") (pin "18") (pinfunction "18_18") (pintype "passive"))
      (node (ref "JTAG") (pin "20") (pinfunction "20_20") (pintype "passive"))
      (node (ref "JTAG") (pin "4") (pinfunction "4_4") (pintype "passive"))
      (node (ref "JTAG") (pin "6") (pinfunction "6_6") (pintype "passive"))
      (node (ref "JTAG") (pin "8") (pinfunction "8_8") (pintype "passive"))
      (node (ref "L3") (pin "1") (pinfunction "1_1") (pintype "passive"))
      (node (ref "L4") (pin "1") (pinfunction "1_1") (pintype "passive"))
      (node (ref "PD") (pin "2") (pinfunction "2_2") (pintype "passive"))
      (node (ref "PD") (pin "20") (pinfunction "20_20") (pintype "passive"))
      (node (ref "PE") (pin "2") (pinfunction "2_2") (pintype "passive"))
      (node (ref "PE") (pin "20") (pinfunction "20_20") (pintype "passive"))
      (node (ref "PF") (pin "2") (pinfunction "2_2") (pintype "passive"))
      (node (ref "PF") (pin "20") (pinfunction "20_20") (pintype "passive"))
      (node (ref "PG") (pin "2") (pinfunction "2_2") (pintype "passive"))
      (node (ref "PG") (pin "20") (pinfunction "20_20") (pintype "passive"))
      (node (ref "PWR_JACK") (pin "-") (pinfunction "-_-") (pintype "passive"))
      (node (ref "PWR_JACK") (pin "--") (pinfunction "--_--") (pintype "passive"))
      (node (ref "PWR_LED") (pin "C") (pinfunction "C_C") (pintype "passive"))
      (node (ref "Q2") (pin "GND") (pinfunction "GND_GND") (pintype "bidirectional"))
      (node (ref "R12") (pin "2") (pinfunction "2_2") (pintype "passive"))
      (node (ref "R2") (pin "2") (pinfunction "2_2") (pintype "passive"))
      (node (ref "R24") (pin "2") (pinfunction "2_2") (pintype "passive"))
      (node (ref "R26") (pin "2") (pinfunction "2_2") (pintype "passive"))
      (node (ref "R31") (pin "2") (pinfunction "2_2") (pintype "passive"))
      (node (ref "R39") (pin "1") (pinfunction "1_1") (pintype "passive"))
      (node (ref "R55") (pin "2") (pinfunction "2_2") (pintype "passive"))
      (node (ref "R56") (pin "2") (pinfunction "2_2") (pintype "passive"))
      (node (ref "R59") (pin "2") (pinfunction "2_2") (pintype "passive"))
      (node (ref "RESET") (pin "P$2") (pinfunction "1_P$2") (pintype "passive"))
      (node (ref "RM2") (pin "1.1") (pinfunction "1_1.1") (pintype "passive"))
      (node (ref "RM2") (pin "2.1") (pinfunction "1_2.1") (pintype "passive"))
      (node (ref "RM2") (pin "4.1") (pinfunction "1_4.1") (pintype "passive"))
      (node (ref "RM3") (pin "1.2") (pinfunction "2_1.2") (pintype "passive"))
      (node (ref "RM3") (pin "2.2") (pinfunction "2_2.2") (pintype "passive"))
      (node (ref "RM3") (pin "3.2") (pinfunction "2_3.2") (pintype "passive"))
      (node (ref "RM3") (pin "4.2") (pinfunction "2_4.2") (pintype "passive"))
      (node (ref "RM4") (pin "2.1") (pinfunction "1_2.1") (pintype "passive"))
      (node (ref "RM5") (pin "1.2") (pinfunction "2_1.2") (pintype "passive"))
      (node (ref "RM5") (pin "2.2") (pinfunction "2_2.2") (pintype "passive"))
      (node (ref "RM5") (pin "3.2") (pinfunction "2_3.2") (pintype "passive"))
      (node (ref "RM6") (pin "1.2") (pinfunction "2_1.2") (pintype "passive"))
      (node (ref "RM6") (pin "4.2") (pinfunction "2_4.2") (pintype "passive"))
      (node (ref "SD/MMC") (pin "6") (pinfunction "VSS_6") (pintype "power_in"))
      (node (ref "U1") (pin "107") (pinfunction "VSS_2_107") (pintype "power_in"))
      (node (ref "U1") (pin "120") (pinfunction "VSS_10_120") (pintype "power_in"))
      (node (ref "U1") (pin "130") (pinfunction "VSS_11_130") (pintype "power_in"))
      (node (ref "U1") (pin "16") (pinfunction "VSS_5_16") (pintype "power_in"))
      (node (ref "U1") (pin "38") (pinfunction "VSS_4_38") (pintype "power_in"))
      (node (ref "U1") (pin "51") (pinfunction "VSS_6_51") (pintype "power_in"))
      (node (ref "U1") (pin "61") (pinfunction "VSS_7_61") (pintype "power_in"))
      (node (ref "U1") (pin "83") (pinfunction "VSS_8_83") (pintype "power_in"))
      (node (ref "U1") (pin "94") (pinfunction "VSS_9_94") (pintype "power_in"))
      (node (ref "U2") (pin "3") (pinfunction "GND_3") (pintype "power_in"))
      (node (ref "U3") (pin "12") (pinfunction "GND2_12") (pintype "power_in"))
      (node (ref "U3") (pin "23") (pinfunction "GND3_23") (pintype "power_in"))
      (node (ref "U3") (pin "35") (pinfunction "GND4_35") (pintype "power_in"))
      (node (ref "U3") (pin "36") (pinfunction "GND5_36") (pintype "power_in"))
      (node (ref "U3") (pin "39") (pinfunction "GND6_39") (pintype "power_in"))
      (node (ref "U3") (pin "43") (pinfunction "GND7_43") (pintype "power_in"))
      (node (ref "U3") (pin "44") (pinfunction "GND8_44") (pintype "power_in"))
      (node (ref "U3") (pin "8") (pinfunction "GND1_8") (pintype "power_in"))
      (node (ref "U4") (pin "GND") (pinfunction "GND_GND") (pintype "bidirectional"))
      (node (ref "U4") (pin "GND@1") (pinfunction "GND_GND@1") (pintype "bidirectional"))
      (node (ref "U5") (pin "2") (pinfunction "2_2") (pintype "power_in"))
      (node (ref "U6") (pin "2") (pinfunction "2_2") (pintype "power_in"))
      (node (ref "U7") (pin "6") (pinfunction "GND_6") (pintype "power_in"))
      (node (ref "U8") (pin "4") (pinfunction "GND_4") (pintype "bidirectional"))
      (node (ref "U9") (pin "2") (pinfunction "GND_2") (pintype "bidirectional"))
      (node (ref "UEXT") (pin "2") (pinfunction "2_2") (pintype "passive"))
      (node (ref "USB_OTG1") (pin "GND") (pinfunction "GND_GND") (pintype "power_in"))
      (node (ref "USB_OTG2") (pin "GND") (pinfunction "GND_GND") (pintype "power_in"))
    )
    (net (code "133") (name "Net-(3.3V_E-Pad1)") (class "Default")
      (node (ref "3.3V_E") (pin "1") (pinfunction "1_1") (pintype "passive"))
      (node (ref "C58") (pin "1") (pinfunction "1_1") (pintype "passive"))
      (node (ref "C59") (pin "1") (pinfunction "1_1") (pintype "passive"))
      (node (ref "C60") (pin "1") (pinfunction "1_1") (pintype "passive"))
      (node (ref "C61") (pin "+") (pinfunction "+_+") (pintype "passive"))
      (node (ref "C62") (pin "1") (pinfunction "1_1") (pintype "passive"))
      (node (ref "L6") (pin "2") (pinfunction "2_2") (pintype "passive"))
      (node (ref "R58") (pin "1") (pinfunction "1_1") (pintype "passive"))
    )
    (net (code "134") (name "Net-(B0_1/B0_0-Pad2)") (class "Default")
      (node (ref "B0_1/B0_0") (pin "2") (pinfunction "2_2") (pintype "passive"))
      (node (ref "R4") (pin "2") (pinfunction "2_2") (pintype "passive"))
    )
    (net (code "135") (name "Net-(B1_1/B1_0-Pad2)") (class "Default")
      (node (ref "B1_1/B1_0") (pin "2") (pinfunction "2_2") (pintype "passive"))
      (node (ref "R9") (pin "2") (pinfunction "2_2") (pintype "passive"))
    )
    (net (code "136") (name "Net-(C21-Pad1)") (class "Default")
      (node (ref "C21") (pin "1") (pinfunction "1_1") (pintype "passive"))
      (node (ref "Q1") (pin "1") (pinfunction "1_1") (pintype "passive"))
      (node (ref "R7") (pin "1") (pinfunction "1_1") (pintype "passive"))
    )
    (net (code "137") (name "Net-(C53-Pad2)") (class "Default")
      (node (ref "C53") (pin "2") (pinfunction "2_2") (pintype "passive"))
      (node (ref "R55") (pin "1") (pinfunction "1_1") (pintype "passive"))
    )
    (net (code "138") (name "Net-(CD1-E{slash}D)") (class "Default")
      (node (ref "CD1") (pin "1") (pinfunction "E/D_1") (pintype "input"))
      (node (ref "R32") (pin "2") (pinfunction "2_2") (pintype "passive"))
    )
    (net (code "139") (name "Net-(D1-A2)") (class "Default")
      (node (ref "3V_BAT") (pin "1") (pinfunction "1_1") (pintype "passive"))
      (node (ref "D1") (pin "2") (pinfunction "A2_2") (pintype "passive"))
    )
    (net (code "140") (name "Net-(L3-Pad2)") (class "Default")
      (node (ref "L3") (pin "2") (pinfunction "2_2") (pintype "passive"))
      (node (ref "USB_OTG1") (pin "GND1") (pinfunction "GND1_GND1") (pintype "input"))
      (node (ref "USB_OTG1") (pin "GND2") (pinfunction "GND2_GND2") (pintype "input"))
      (node (ref "USB_OTG1") (pin "GND3") (pinfunction "GND3_GND3") (pintype "input"))
      (node (ref "USB_OTG1") (pin "GND4") (pinfunction "GND4_GND4") (pintype "input"))
    )
    (net (code "141") (name "Net-(L4-Pad2)") (class "Default")
      (node (ref "L4") (pin "2") (pinfunction "2_2") (pintype "passive"))
      (node (ref "USB_OTG2") (pin "GND1") (pinfunction "GND1_GND1") (pintype "input"))
      (node (ref "USB_OTG2") (pin "GND2") (pinfunction "GND2_GND2") (pintype "input"))
      (node (ref "USB_OTG2") (pin "GND3") (pinfunction "GND3_GND3") (pintype "input"))
      (node (ref "USB_OTG2") (pin "GND4") (pinfunction "GND4_GND4") (pintype "input"))
    )
    (net (code "142") (name "Net-(LAN-NC)") (class "Default")
      (node (ref "C27") (pin "2") (pinfunction "2_2") (pintype "passive"))
      (node (ref "LAN") (pin "6") (pinfunction "NC_6") (pintype "bidirectional"))
      (node (ref "R14") (pin "1") (pinfunction "1_1") (pintype "passive"))
    )
    (net (code "143") (name "Net-(LAN-RD+)") (class "Default")
      (node (ref "LAN") (pin "7") (pinfunction "RD+_7") (pintype "bidirectional"))
      (node (ref "R15") (pin "1") (pinfunction "1_1") (pintype "passive"))
      (node (ref "U3") (pin "33") (pinfunction "RX+_33") (pintype "input"))
    )
    (net (code "144") (name "Net-(LAN-RD-)") (class "Default")
      (node (ref "LAN") (pin "8") (pinfunction "RD-_8") (pintype "bidirectional"))
      (node (ref "R13") (pin "1") (pinfunction "1_1") (pintype "passive"))
      (node (ref "U3") (pin "32") (pinfunction "RX-_32") (pintype "input"))
    )
    (net (code "145") (name "Net-(LAN-TD+)") (class "Default")
      (node (ref "LAN") (pin "1") (pinfunction "TD+_1") (pintype "bidirectional"))
      (node (ref "R17") (pin "1") (pinfunction "1_1") (pintype "passive"))
      (node (ref "U3") (pin "41") (pinfunction "TX+_41") (pintype "output"))
    )
    (net (code "146") (name "Net-(LAN-TD-)") (class "Default")
      (node (ref "LAN") (pin "2") (pinfunction "TD-_2") (pintype "bidirectional"))
      (node (ref "R16") (pin "1") (pinfunction "1_1") (pintype "passive"))
      (node (ref "U3") (pin "40") (pinfunction "TX-_40") (pintype "output"))
    )
    (net (code "147") (name "Net-(LED-PadA)") (class "Default")
      (node (ref "LED") (pin "A") (pinfunction "A_A") (pintype "passive"))
      (node (ref "R40") (pin "1") (pinfunction "1_1") (pintype "passive"))
    )
    (net (code "148") (name "Net-(PD-Pad5)") (class "Default")
      (node (ref "PD") (pin "5") (pinfunction "5_5") (pintype "passive"))
      (node (ref "R49") (pin "1") (pinfunction "1_1") (pintype "passive"))
    )
    (net (code "149") (name "Net-(PE-Pad5)") (class "Default")
      (node (ref "PE") (pin "5") (pinfunction "5_5") (pintype "passive"))
      (node (ref "PE2_E") (pin "2") (pinfunction "2_2") (pintype "passive"))
    )
    (net (code "150") (name "Net-(PE-Pad7)") (class "Default")
      (node (ref "PE") (pin "7") (pinfunction "7_7") (pintype "passive"))
      (node (ref "PE4_E") (pin "2") (pinfunction "2_2") (pintype "passive"))
    )
    (net (code "151") (name "Net-(PE-Pad8)") (class "Default")
      (node (ref "PE") (pin "8") (pinfunction "8_8") (pintype "passive"))
      (node (ref "PE5_E") (pin "1") (pinfunction "1_1") (pintype "passive"))
    )
    (net (code "152") (name "Net-(PE-Pad9)") (class "Default")
      (node (ref "PE") (pin "9") (pinfunction "9_9") (pintype "passive"))
      (node (ref "PE6_E") (pin "2") (pinfunction "2_2") (pintype "passive"))
    )
    (net (code "153") (name "Net-(PF-Pad9)") (class "Default")
      (node (ref "PF") (pin "9") (pinfunction "9_9") (pintype "passive"))
      (node (ref "PF6_E") (pin "2") (pinfunction "2_2") (pintype "passive"))
    )
    (net (code "154") (name "Net-(PF-Pad10)") (class "Default")
      (node (ref "PF") (pin "10") (pinfunction "10_10") (pintype "passive"))
      (node (ref "PF7_E") (pin "1") (pinfunction "1_1") (pintype "passive"))
    )
    (net (code "155") (name "Net-(PF-Pad11)") (class "Default")
      (node (ref "PF") (pin "11") (pinfunction "11_11") (pintype "passive"))
      (node (ref "PF8_E") (pin "2") (pinfunction "2_2") (pintype "passive"))
    )
    (net (code "156") (name "Net-(PF-Pad12)") (class "Default")
      (node (ref "PF") (pin "12") (pinfunction "12_12") (pintype "passive"))
      (node (ref "PF9_E") (pin "1") (pinfunction "1_1") (pintype "passive"))
    )
    (net (code "157") (name "Net-(PF-Pad13)") (class "Default")
      (node (ref "PF") (pin "13") (pinfunction "13_13") (pintype "passive"))
      (node (ref "PF10_E") (pin "2") (pinfunction "2_2") (pintype "passive"))
    )
    (net (code "158") (name "Net-(PF-Pad14)") (class "Default")
      (node (ref "PF") (pin "14") (pinfunction "14_14") (pintype "passive"))
      (node (ref "PF11_E") (pin "1") (pinfunction "1_1") (pintype "passive"))
    )
    (net (code "159") (name "Net-(PG-Pad10)") (class "Default")
      (node (ref "PG") (pin "10") (pinfunction "10_10") (pintype "passive"))
      (node (ref "PG7_E") (pin "1") (pinfunction "1_1") (pintype "passive"))
    )
    (net (code "160") (name "Net-(PG-Pad11)") (class "Default")
      (node (ref "PG") (pin "11") (pinfunction "11_11") (pintype "passive"))
      (node (ref "PG8_E") (pin "2") (pinfunction "2_2") (pintype "passive"))
    )
    (net (code "161") (name "Net-(PG-Pad13)") (class "Default")
      (node (ref "PG") (pin "13") (pinfunction "13_13") (pintype "passive"))
      (node (ref "R50") (pin "1") (pinfunction "1_1") (pintype "passive"))
    )
    (net (code "162") (name "Net-(PG-Pad14)") (class "Default")
      (node (ref "PG") (pin "14") (pinfunction "14_14") (pintype "passive"))
      (node (ref "R51") (pin "2") (pinfunction "2_2") (pintype "passive"))
    )
    (net (code "163") (name "Net-(PG-Pad15)") (class "Default")
      (node (ref "PG") (pin "15") (pinfunction "15_15") (pintype "passive"))
      (node (ref "PG12_E") (pin "2") (pinfunction "2_2") (pintype "passive"))
    )
    (net (code "164") (name "Net-(PG-Pad16)") (class "Default")
      (node (ref "PG") (pin "16") (pinfunction "16_16") (pintype "passive"))
      (node (ref "R52") (pin "2") (pinfunction "2_2") (pintype "passive"))
    )
    (net (code "165") (name "Net-(PG-Pad17)") (class "Default")
      (node (ref "PG") (pin "17") (pinfunction "17_17") (pintype "passive"))
      (node (ref "R53") (pin "1") (pinfunction "1_1") (pintype "passive"))
    )
    (net (code "166") (name "Net-(PG-Pad18)") (class "Default")
      (node (ref "PG") (pin "18") (pinfunction "18_18") (pintype "passive"))
      (node (ref "PG15_E") (pin "1") (pinfunction "1_1") (pintype "passive"))
    )
    (net (code "167") (name "Net-(PWR_LED-PadA)") (class "Default")
      (node (ref "PWR_LED") (pin "A") (pinfunction "A_A") (pintype "passive"))
      (node (ref "R60") (pin "2") (pinfunction "2_2") (pintype "passive"))
    )
    (net (code "168") (name "Net-(R1-1.1)") (class "Default")
      (node (ref "C3") (pin "2") (pinfunction "2_2") (pintype "passive"))
      (node (ref "R1") (pin "1") (pinfunction "1.1_1") (pintype "passive"))
      (node (ref "R2") (pin "1") (pinfunction "1_1") (pintype "passive"))
      (node (ref "U1") (pin "143") (pinfunction "VDD_3_143") (pintype "power_in"))
    )
    (net (code "169") (name "Net-(R24-Pad1)") (class "Default")
      (node (ref "R24") (pin "1") (pinfunction "1_1") (pintype "passive"))
      (node (ref "R25") (pin "1") (pinfunction "1_1") (pintype "passive"))
    )
    (net (code "170") (name "Net-(R44-Pad2)") (class "Default")
      (node (ref "R44") (pin "2") (pinfunction "2_2") (pintype "passive"))
      (node (ref "U5") (pin "6") (pinfunction "6_6") (pintype "bidirectional"))
    )
    (net (code "171") (name "Net-(R45-Pad2)") (class "Default")
      (node (ref "R45") (pin "2") (pinfunction "2_2") (pintype "passive"))
      (node (ref "U5") (pin "4") (pinfunction "4_4") (pintype "bidirectional"))
    )
    (net (code "172") (name "Net-(R47-Pad2)") (class "Default")
      (node (ref "R47") (pin "2") (pinfunction "2_2") (pintype "passive"))
      (node (ref "U6") (pin "4") (pinfunction "4_4") (pintype "bidirectional"))
    )
    (net (code "173") (name "Net-(R48-Pad2)") (class "Default")
      (node (ref "R48") (pin "2") (pinfunction "2_2") (pintype "passive"))
      (node (ref "U6") (pin "6") (pinfunction "6_6") (pintype "bidirectional"))
    )
    (net (code "174") (name "Net-(RESET-0)") (class "Default")
      (node (ref "C19") (pin "2") (pinfunction "2_2") (pintype "passive"))
      (node (ref "R5") (pin "1") (pinfunction "1_1") (pintype "passive"))
      (node (ref "R6") (pin "2") (pinfunction "2_2") (pintype "passive"))
      (node (ref "RESET") (pin "P$1") (pinfunction "0_P$1") (pintype "passive"))
      (node (ref "U2") (pin "1") (pinfunction "RESET_1") (pintype "output"))
    )
    (net (code "175") (name "Net-(RM2A-2)") (class "Default")
      (node (ref "RM2") (pin "1.2") (pinfunction "2_1.2") (pintype "passive"))
      (node (ref "U3") (pin "19") (pinfunction "TXD2_19") (pintype "input"))
    )
    (net (code "176") (name "Net-(RM2B-2)") (class "Default")
      (node (ref "RM2") (pin "2.2") (pinfunction "2_2.2") (pintype "passive"))
      (node (ref "U3") (pin "20") (pinfunction "TXD3_20") (pintype "input"))
    )
    (net (code "177") (name "Net-(RM2C-2)") (class "Default")
      (node (ref "RM2") (pin "3.2") (pinfunction "2_3.2") (pintype "passive"))
      (node (ref "U3") (pin "21") (pinfunction "COL/RMII_21") (pintype "bidirectional"))
    )
    (net (code "178") (name "Net-(RM2D-2)") (class "Default")
      (node (ref "RM2") (pin "4.2") (pinfunction "2_4.2") (pintype "passive"))
      (node (ref "U3") (pin "22") (pinfunction "CRS/RMII_BTB_22") (pintype "bidirectional"))
    )
    (net (code "179") (name "Net-(RM3C-1)") (class "Default")
      (node (ref "RM3") (pin "3.1") (pinfunction "1_3.1") (pintype "passive"))
      (node (ref "U3") (pin "4") (pinfunction "RXD2/PHYAD2_4") (pintype "bidirectional"))
    )
    (net (code "180") (name "Net-(RM3D-1)") (class "Default")
      (node (ref "RM3") (pin "4.1") (pinfunction "1_4.1") (pintype "passive"))
      (node (ref "U3") (pin "3") (pinfunction "RXD3/PHYAD1_3") (pintype "bidirectional"))
    )
    (net (code "181") (name "Net-(RM5B-1)") (class "Default")
      (node (ref "JTAG") (pin "17") (pinfunction "17_17") (pintype "passive"))
      (node (ref "RM5") (pin "2.1") (pinfunction "1_2.1") (pintype "passive"))
    )
    (net (code "182") (name "Net-(RM5C-1)") (class "Default")
      (node (ref "JTAG") (pin "11") (pinfunction "11_11") (pintype "passive"))
      (node (ref "R33") (pin "1") (pinfunction "1_1") (pintype "passive"))
      (node (ref "RM5") (pin "3.1") (pinfunction "1_3.1") (pintype "passive"))
    )
    (net (code "183") (name "Net-(SD/MMC-VDD)") (class "Default")
      (node (ref "C22") (pin "1") (pinfunction "1_1") (pintype "passive"))
      (node (ref "C23") (pin "1") (pinfunction "1_1") (pintype "passive"))
      (node (ref "L2") (pin "2") (pinfunction "2_2") (pintype "passive"))
      (node (ref "SD/MMC") (pin "4") (pinfunction "VDD_4") (pintype "power_in"))
    )
    (net (code "184") (name "Net-(U1-PC14{slash}OSC32_IN)") (class "Default")
      (node (ref "C24") (pin "1") (pinfunction "1_1") (pintype "passive"))
      (node (ref "Q2") (pin "2") (pinfunction "2_2") (pintype "passive"))
      (node (ref "R10") (pin "2") (pinfunction "2_2") (pintype "passive"))
      (node (ref "U1") (pin "8") (pinfunction "PC14/OSC32_IN_8") (pintype "bidirectional"))
    )
    (net (code "185") (name "Net-(U1-PC15{slash}OSC32_OUT)") (class "Default")
      (node (ref "C25") (pin "1") (pinfunction "1_1") (pintype "passive"))
      (node (ref "Q2") (pin "1") (pinfunction "1_1") (pintype "passive"))
      (node (ref "R10") (pin "1") (pinfunction "1_1") (pintype "passive"))
      (node (ref "U1") (pin "9") (pinfunction "PC15/OSC32_OUT_9") (pintype "bidirectional"))
    )
    (net (code "186") (name "Net-(U1-PH0{slash}OSC_IN)") (class "Default")
      (node (ref "C20") (pin "1") (pinfunction "1_1") (pintype "passive"))
      (node (ref "Q1") (pin "2") (pinfunction "2_2") (pintype "passive"))
      (node (ref "R8") (pin "2") (pinfunction "2_2") (pintype "passive"))
      (node (ref "U1") (pin "23") (pinfunction "PH0/OSC_IN_23") (pintype "input"))
    )
    (net (code "187") (name "Net-(U1-PH1{slash}OSC_OUT)") (class "Default")
      (node (ref "R7") (pin "2") (pinfunction "2_2") (pintype "passive"))
      (node (ref "R8") (pin "1") (pinfunction "1_1") (pintype "passive"))
      (node (ref "U1") (pin "24") (pinfunction "PH1/OSC_OUT_24") (pintype "output"))
    )
    (net (code "188") (name "Net-(U1-VCAP_1)") (class "Default")
      (node (ref "C14") (pin "2") (pinfunction "2_2") (pintype "passive"))
      (node (ref "U1") (pin "71") (pinfunction "VCAP_1_71") (pintype "output"))
    )
    (net (code "189") (name "Net-(U1-VCAP_2)") (class "Default")
      (node (ref "C15") (pin "2") (pinfunction "2_2") (pintype "passive"))
      (node (ref "U1") (pin "106") (pinfunction "VCAP_2_106") (pintype "output"))
    )
    (net (code "190") (name "Net-(U1-VREF+)") (class "Default")
      (node (ref "C18") (pin "2") (pinfunction "2_2") (pintype "passive"))
      (node (ref "R3") (pin "2") (pinfunction "2_2") (pintype "passive"))
      (node (ref "U1") (pin "32") (pinfunction "VREF+_32") (pintype "power_in"))
    )
    (net (code "191") (name "Net-(U3-INT{slash}PHYAD0)") (class "Default")
      (node (ref "R22") (pin "2") (pinfunction "2_2") (pintype "passive"))
      (node (ref "U3") (pin "25") (pinfunction "INT/PHYAD0_25") (pintype "bidirectional"))
    )
    (net (code "192") (name "Net-(U3-LED0{slash}TEST)") (class "Default")
      (node (ref "R21") (pin "2") (pinfunction "2_2") (pintype "passive"))
      (node (ref "U3") (pin "26") (pinfunction "LED0/TEST_26") (pintype "bidirectional"))
    )
    (net (code "193") (name "Net-(U3-LED1{slash}SPD100{slash}NFEF)") (class "Default")
      (node (ref "R20") (pin "2") (pinfunction "2_2") (pintype "passive"))
      (node (ref "U3") (pin "27") (pinfunction "LED1/SPD100/NFEF_27") (pintype "bidirectional"))
    )
    (net (code "194") (name "Net-(U3-LED2{slash}DUPLEX)") (class "Default")
      (node (ref "R19") (pin "2") (pinfunction "2_2") (pintype "passive"))
      (node (ref "U3") (pin "28") (pinfunction "LED2/DUPLEX_28") (pintype "bidirectional"))
    )
    (net (code "195") (name "Net-(U3-PD#)") (class "Default")
      (node (ref "R18") (pin "2") (pinfunction "2_2") (pintype "passive"))
      (node (ref "U3") (pin "30") (pinfunction "PD#_30") (pintype "input"))
    )
    (net (code "196") (name "Net-(U3-REXT)") (class "Default")
      (node (ref "R25") (pin "2") (pinfunction "2_2") (pintype "passive"))
      (node (ref "U3") (pin "37") (pinfunction "REXT_37") (pintype "input"))
    )
    (net (code "197") (name "Net-(U3-TXER)") (class "Default")
      (node (ref "R26") (pin "1") (pinfunction "1_1") (pintype "passive"))
      (node (ref "U3") (pin "14") (pinfunction "TXER_14") (pintype "input"))
    )
    (net (code "198") (name "Net-(U3-VDDC)") (class "Default")
      (node (ref "C32") (pin "1") (pinfunction "1_1") (pintype "passive"))
      (node (ref "C33") (pin "1") (pinfunction "1_1") (pintype "passive"))
      (node (ref "FB2") (pin "2") (pinfunction "2_2") (pintype "passive"))
      (node (ref "U3") (pin "13") (pinfunction "VDDC_13") (pintype "power_in"))
    )
    (net (code "199") (name "Net-(U3-XI)") (class "Default")
      (node (ref "R27") (pin "2") (pinfunction "2_2") (pintype "passive"))
      (node (ref "U3") (pin "46") (pinfunction "XI_46") (pintype "input"))
    )
    (net (code "200") (name "Net-(U8-BS)") (class "Default")
      (node (ref "C52") (pin "1") (pinfunction "1_1") (pintype "passive"))
      (node (ref "U8") (pin "1") (pinfunction "BS_1") (pintype "bidirectional"))
    )
    (net (code "201") (name "Net-(U8-COMP)") (class "Default")
      (node (ref "C53") (pin "1") (pinfunction "1_1") (pintype "passive"))
      (node (ref "U8") (pin "6") (pinfunction "COMP_6") (pintype "bidirectional"))
    )
    (net (code "202") (name "Net-(U8-EN)") (class "Default")
      (node (ref "R54") (pin "2") (pinfunction "2_2") (pintype "passive"))
      (node (ref "U8") (pin "7") (pinfunction "EN_7") (pintype "bidirectional"))
    )
    (net (code "203") (name "Net-(U8-FB)") (class "Default")
      (node (ref "R56") (pin "1") (pinfunction "1_1") (pintype "passive"))
      (node (ref "R57") (pin "1") (pinfunction "1_1") (pintype "passive"))
      (node (ref "U8") (pin "5") (pinfunction "FB_5") (pintype "bidirectional"))
    )
    (net (code "204") (name "Net-(U8-SS)") (class "Default")
      (node (ref "C51") (pin "1") (pinfunction "1_1") (pintype "passive"))
      (node (ref "U8") (pin "8") (pinfunction "SS_8") (pintype "bidirectional"))
    )
    (net (code "205") (name "Net-(U8-SW)") (class "Default")
      (node (ref "C52") (pin "2") (pinfunction "2_2") (pintype "passive"))
      (node (ref "L5") (pin "1") (pinfunction "1_1") (pintype "passive"))
      (node (ref "U8") (pin "3") (pinfunction "SW_3") (pintype "bidirectional"))
    )
    (net (code "206") (name "Net-(U9-FB)") (class "Default")
      (node (ref "C58") (pin "2") (pinfunction "2_2") (pintype "passive"))
      (node (ref "R58") (pin "2") (pinfunction "2_2") (pintype "passive"))
      (node (ref "R59") (pin "1") (pinfunction "1_1") (pintype "passive"))
      (node (ref "U9") (pin "5") (pinfunction "FB_5") (pintype "bidirectional"))
    )
    (net (code "207") (name "Net-(U9-LX)") (class "Default")
      (node (ref "L6") (pin "1") (pinfunction "1_1") (pintype "passive"))
      (node (ref "U9") (pin "3") (pinfunction "LX_3") (pintype "bidirectional"))
    )
    (net (code "208") (name "Net-(WKUP-1)") (class "Default")
      (node (ref "C38") (pin "1") (pinfunction "1_1") (pintype "passive"))
      (node (ref "R38") (pin "1") (pinfunction "1_1") (pintype "passive"))
      (node (ref "R39") (pin "2") (pinfunction "2_2") (pintype "passive"))
      (node (ref "WKUP") (pin "P$2") (pinfunction "1_P$2") (pintype "passive"))
    )
    (net (code "209") (name "VIN") (class "Default")
      (node (ref "C50") (pin "+") (pinfunction "+_+") (pintype "passive"))
      (node (ref "CON1") (pin "6") (pinfunction "6_6") (pintype "passive"))
      (node (ref "D4") (pin "C") (pinfunction "C_C") (pintype "passive"))
      (node (ref "PWR_JACK") (pin "+") (pinfunction "+_+") (pintype "passive"))
      (node (ref "R54") (pin "1") (pinfunction "1_1") (pintype "passive"))
      (node (ref "U4") (pin "VIN") (pinfunction "VIN_VIN") (pintype "bidirectional"))
      (node (ref "U8") (pin "2") (pinfunction "IN_2") (pintype "bidirectional"))
    )
    (net (code "210") (name "unconnected-(U3-FXSD{slash}FXEN-Pad34)") (class "Default")
      (node (ref "U3") (pin "34") (pinfunction "FXSD/FXEN_34") (pintype "bidirectional"))
    )
    (net (code "211") (name "unconnected-(U3-LED3{slash}NWAYEN-Pad29)") (class "Default")
      (node (ref "U3") (pin "29") (pinfunction "LED3/NWAYEN_29") (pintype "bidirectional"))
    )
    (net (code "212") (name "unconnected-(U3-RXC-Pad10)") (class "Default")
      (node (ref "U3") (pin "10") (pinfunction "RXC_10") (pintype "output"))
    )
    (net (code "213") (name "unconnected-(U3-RXER{slash}ISO-Pad11)") (class "Default")
      (node (ref "U3") (pin "11") (pinfunction "RXER/ISO_11") (pintype "bidirectional"))
    )
    (net (code "214") (name "unconnected-(U3-XO-Pad45)") (class "Default")
      (node (ref "U3") (pin "45") (pinfunction "XO_45") (pintype "output"))
    )
  )
)
